# Audio_Test_Board.net
KiCad netlist of a schematic drawn in EAGLE
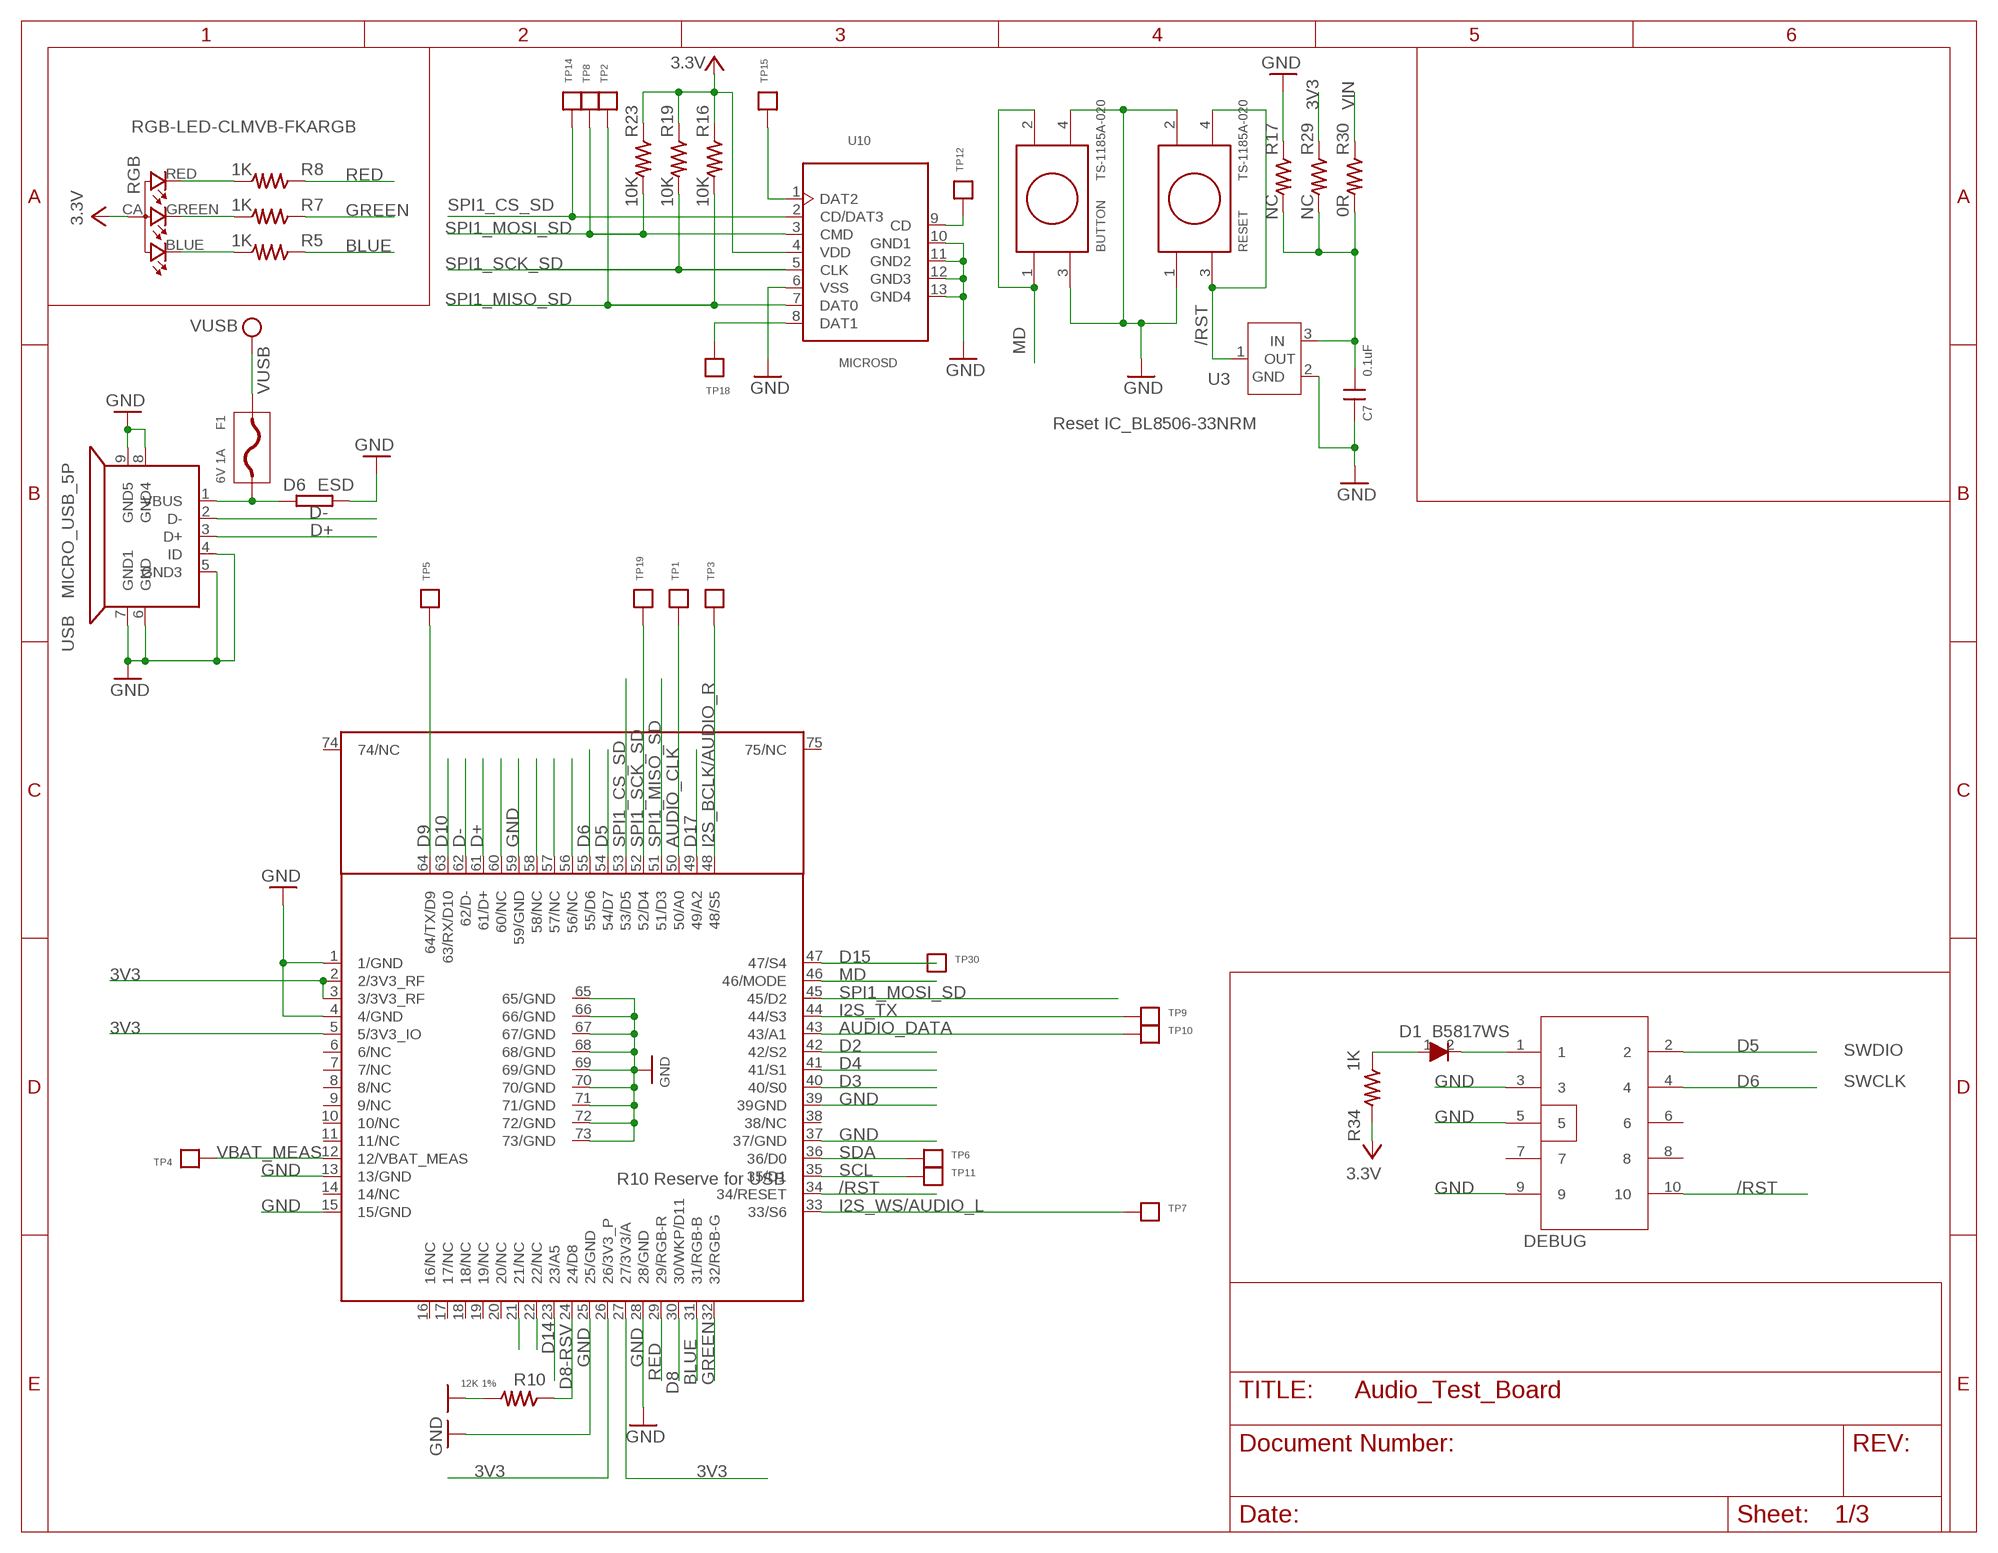
[diagram p0: schematic, sheet 1]
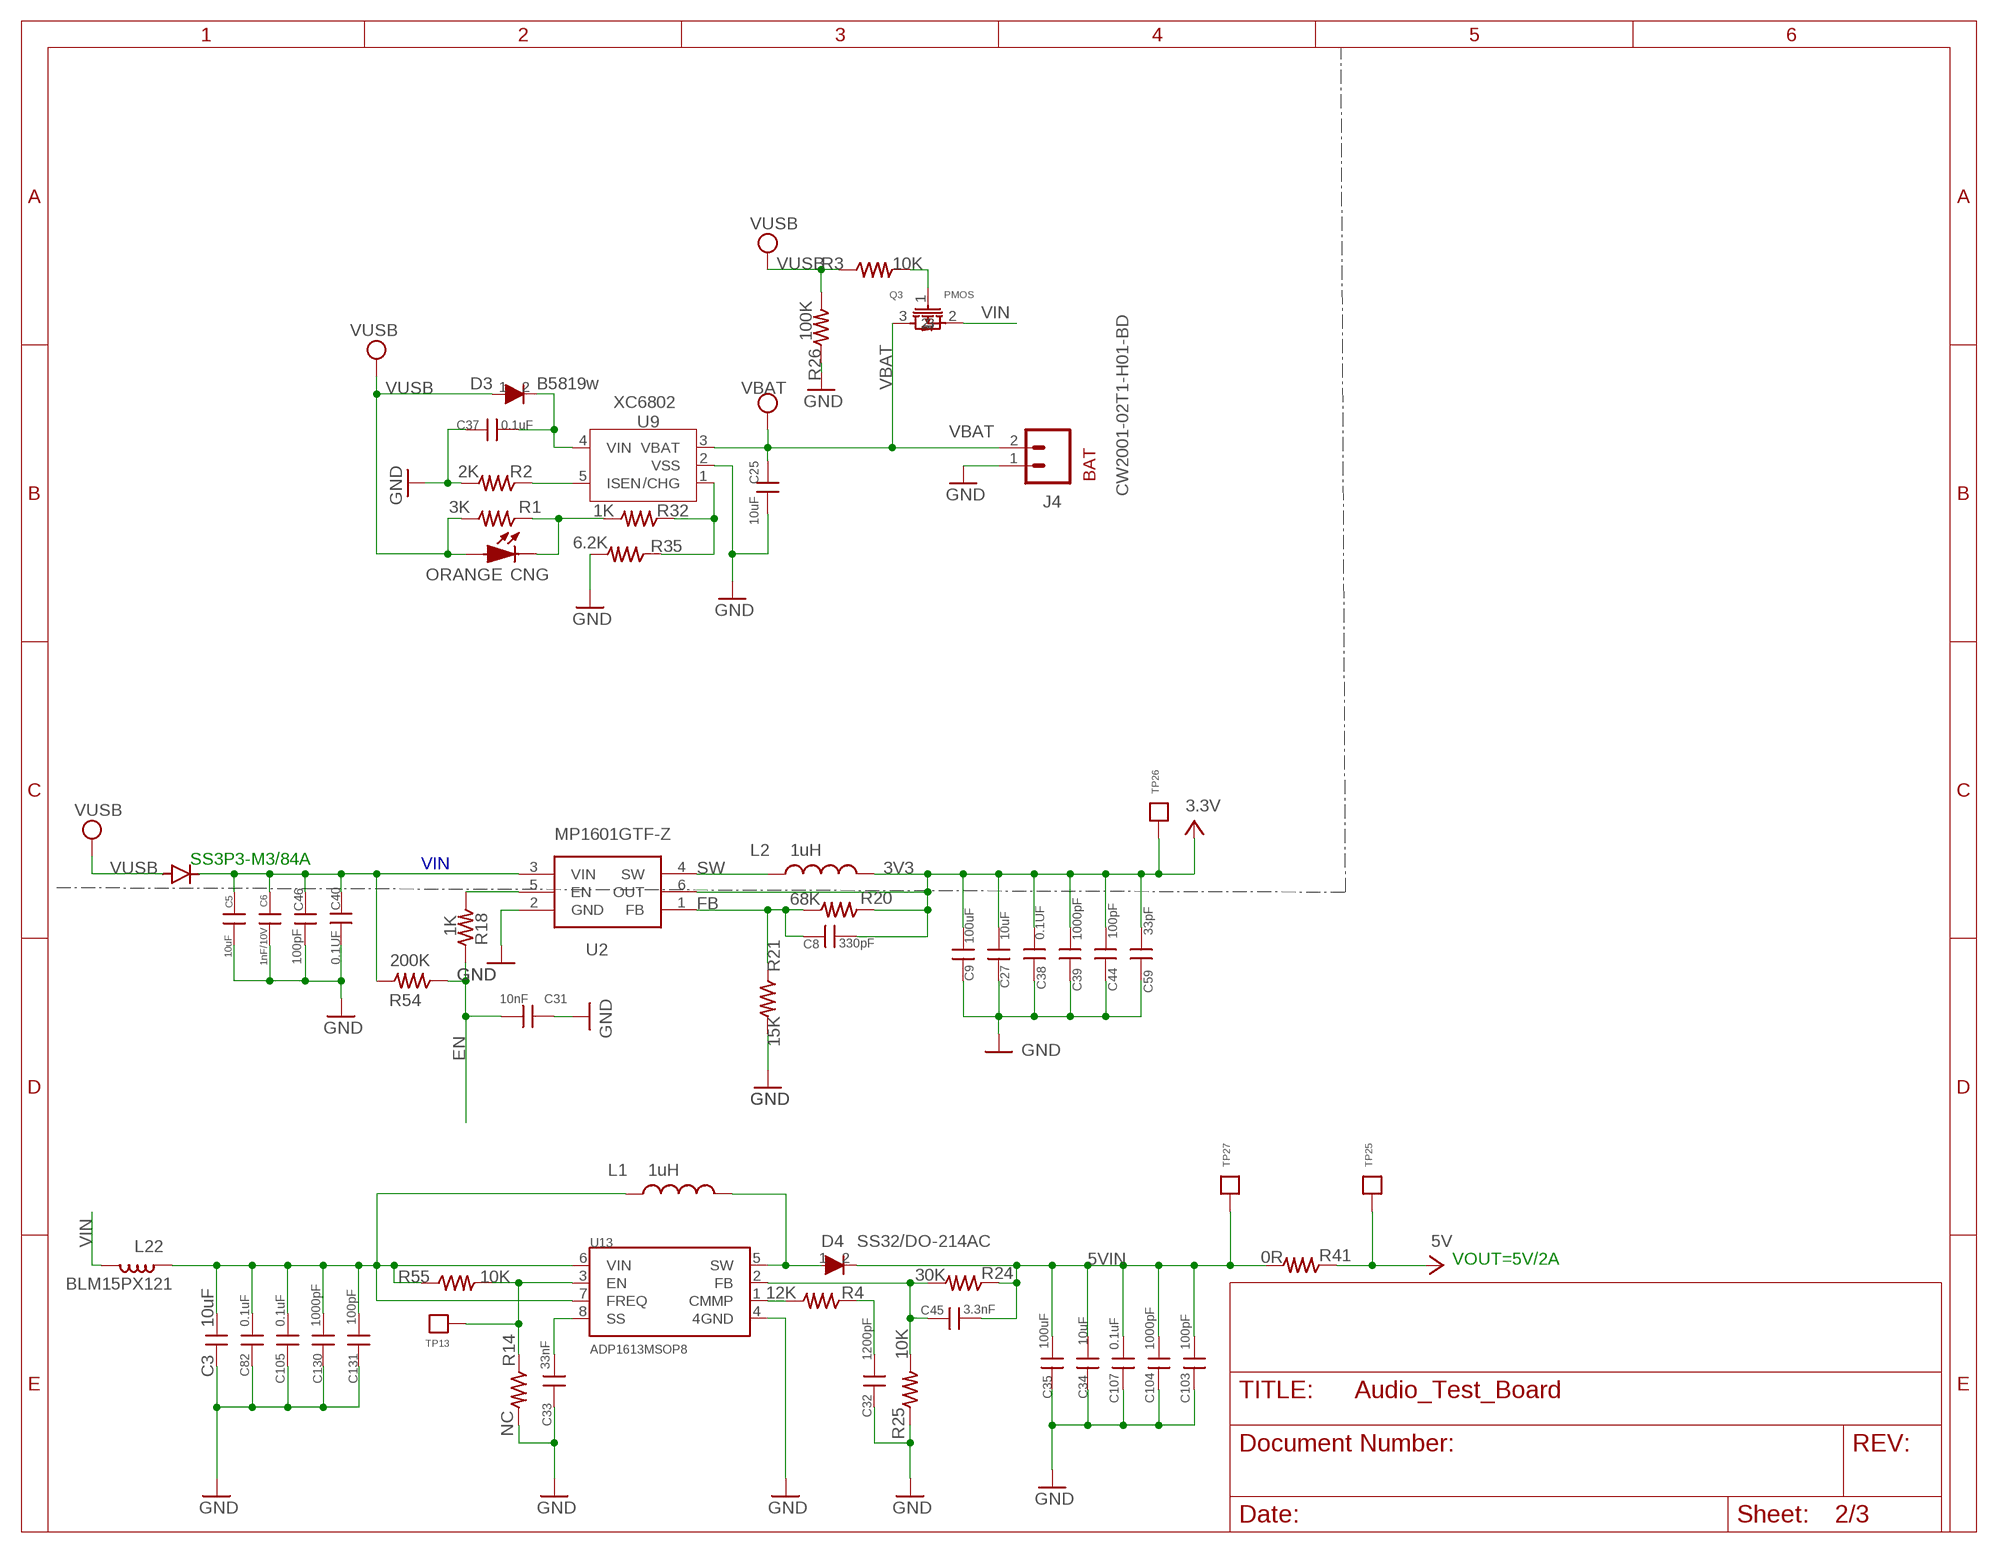
[diagram p1: schematic, sheet 2]
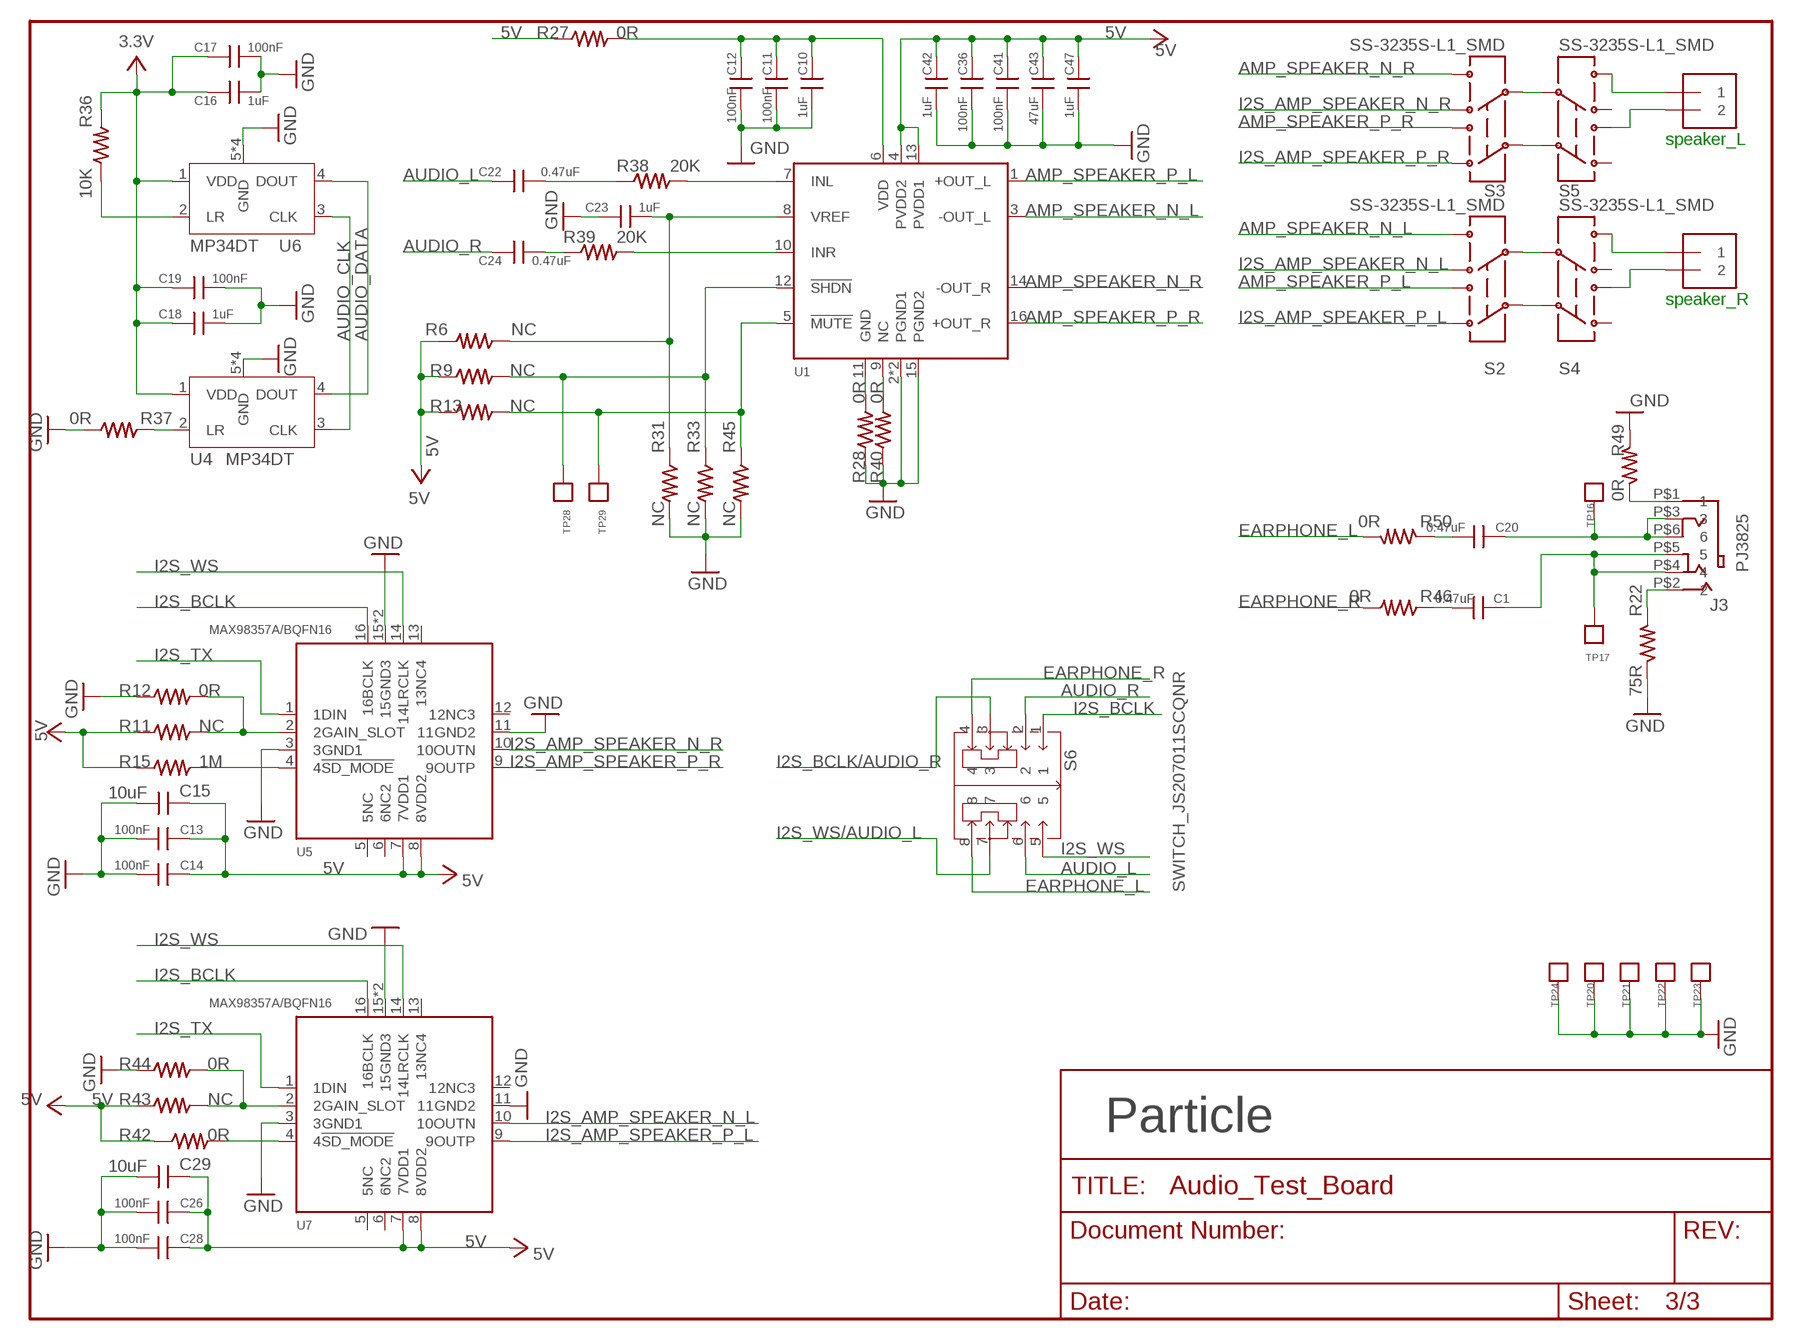
[diagram p2: schematic, sheet 3]

(export (version "E")
  (design (tool "Eeschema 10.0.6"))
  (components
    (comp (ref "C3")
      (value "10uF")
      (footprint "eagle-import:C0603")
      (libsource (lib "eagle-import") (part "particle SZ_CAPC0603"))
    )
    (comp (ref "C5")
      (value "10uF")
      (footprint "eagle-import:C0603")
      (libsource (lib "eagle-import") (part "particle SZ_CAPC0603"))
    )
    (comp (ref "C6")
      (value "1nF/10V")
      (footprint "eagle-import:C-0402")
      (libsource (lib "eagle-import") (part "particle SZ_CAP0402"))
    )
    (comp (ref "C8")
      (value "330pF")
      (footprint "eagle-import:C0402")
      (libsource (lib "eagle-import") (part "particle SZ_CAP0402A"))
    )
    (comp (ref "C9")
      (value "100uF")
      (footprint "eagle-import:C1206")
      (libsource (lib "eagle-import") (part "particle SZ_CAPC1206"))
    )
    (comp (ref "C25")
      (value "10uF")
      (footprint "eagle-import:C0805")
      (libsource (lib "eagle-import") (part "CAPC0805"))
    )
    (comp (ref "C27")
      (value "10uF")
      (footprint "eagle-import:C0603")
      (libsource (lib "eagle-import") (part "particle SZ_CAPC0603"))
    )
    (comp (ref "C31")
      (value "10nF")
      (footprint "eagle-import:C-0402")
      (libsource (lib "eagle-import") (part "particle SZ_CAP0402"))
    )
    (comp (ref "C32")
      (value "1200pF")
      (footprint "eagle-import:C-0402")
      (libsource (lib "eagle-import") (part "particle SZ_CAP0402"))
    )
    (comp (ref "C33")
      (value "33nF")
      (footprint "eagle-import:C-0402")
      (libsource (lib "eagle-import") (part "particle SZ_CAP0402"))
    )
    (comp (ref "C34")
      (value "10uF")
      (footprint "eagle-import:C0603")
      (libsource (lib "eagle-import") (part "particle SZ_CAPC0603"))
    )
    (comp (ref "C35")
      (value "100uF")
      (footprint "eagle-import:C1206")
      (libsource (lib "eagle-import") (part "particle SZ_CAPC1206"))
    )
    (comp (ref "C37")
      (value "0.1uF")
      (footprint "eagle-import:C-0402")
      (libsource (lib "eagle-import") (part "CAP0402"))
    )
    (comp (ref "C38")
      (value "0.1UF")
      (footprint "eagle-import:C-0402")
      (libsource (lib "eagle-import") (part "CAP0402"))
    )
    (comp (ref "C39")
      (value "1000pF")
      (footprint "eagle-import:C-0402")
      (libsource (lib "eagle-import") (part "CAP0402"))
    )
    (comp (ref "C40")
      (value "0.1UF")
      (footprint "eagle-import:C-0402")
      (libsource (lib "eagle-import") (part "CAP0402"))
    )
    (comp (ref "C44")
      (value "100pF")
      (footprint "eagle-import:C-0402")
      (libsource (lib "eagle-import") (part "CAP0402"))
    )
    (comp (ref "C45")
      (value "3.3nF")
      (footprint "eagle-import:C0402")
      (libsource (lib "eagle-import") (part "particle SZ_CAP0402A"))
    )
    (comp (ref "C46")
      (value "100pF")
      (footprint "eagle-import:C-0402")
      (libsource (lib "eagle-import") (part "CAP0402"))
    )
    (comp (ref "C59")
      (value "33pF")
      (footprint "eagle-import:C-0402")
      (libsource (lib "eagle-import") (part "CAP0402"))
    )
    (comp (ref "C82")
      (value "0.1uF")
      (footprint "eagle-import:C0402")
      (libsource (lib "eagle-import") (part "particle SZ_CAP0402A"))
    )
    (comp (ref "C103")
      (value "100pF")
      (footprint "eagle-import:C-0402")
      (libsource (lib "eagle-import") (part "particle SZ_CAP0402"))
    )
    (comp (ref "C104")
      (value "1000pF")
      (footprint "eagle-import:C-0402")
      (libsource (lib "eagle-import") (part "particle SZ_CAP0402"))
    )
    (comp (ref "C105")
      (value "0.1uF")
      (footprint "eagle-import:C0402")
      (libsource (lib "eagle-import") (part "particle SZ_CAP0402A"))
    )
    (comp (ref "C107")
      (value "0.1uF")
      (footprint "eagle-import:C-0402")
      (libsource (lib "eagle-import") (part "particle SZ_CAP0402"))
    )
    (comp (ref "C130")
      (value "1000pF")
      (footprint "eagle-import:C0402")
      (libsource (lib "eagle-import") (part "particle SZ_CAP0402A"))
    )
    (comp (ref "C131")
      (value "100pF")
      (footprint "eagle-import:C-0402")
      (libsource (lib "eagle-import") (part "particle SZ_CAP0402"))
    )
    (comp (ref "CNG")
      (value "ORANGE")
      (footprint "eagle-import:LED0603")
      (libsource (lib "eagle-import") (part "LED"))
    )
    (comp (ref "D2")
      (value "SS3P3-M3/84A")
      (footprint "eagle-import:DIODE-DO-220AA_NT(SMP)")
      (libsource (lib "eagle-import") (part "DIODE_NT"))
    )
    (comp (ref "D3")
      (value "B5819w")
      (footprint "eagle-import:SOD-123")
      (libsource (lib "eagle-import") (part "DIODESOD123"))
    )
    (comp (ref "D4")
      (value "SS32/DO-214AC")
      (footprint "eagle-import:DO-214AC")
      (libsource (lib "eagle-import") (part "SS32DO-214AC"))
    )
    (comp (ref "J4")
      (value "CW2001-02T1-H01-BD")
      (footprint "eagle-import:JST-2-SMD")
      (libsource (lib "eagle-import") (part "CONN_02-JST-2MM-SMT"))
    )
    (comp (ref "L1")
      (value "1uH")
      (footprint "eagle-import:INDUCTOR-VLS-E")
      (libsource (lib "eagle-import") (part "INDUCTOR-SPARKFUNVLS3012ET-4R7M"))
    )
    (comp (ref "L2")
      (value "1uH")
      (footprint "eagle-import:INDUCTOR-VLS-E")
      (libsource (lib "eagle-import") (part "INDUCTOR-SPARKFUNVLS3012ET-4R7M"))
    )
    (comp (ref "L22")
      (value "BLM15PX121")
      (footprint "eagle-import:R-0402S")
      (libsource (lib "eagle-import") (part "L-2PIN"))
    )
    (comp (ref "Q3")
      (value "PMOS")
      (footprint "eagle-import:SOT-23")
      (libsource (lib "eagle-import") (part "PMOS"))
    )
    (comp (ref "R1")
      (value "3K")
      (footprint "eagle-import:R-0402S")
      (libsource (lib "eagle-import") (part "particle SZ_RES0402S"))
    )
    (comp (ref "R2")
      (value "2K")
      (footprint "eagle-import:R-0402S")
      (libsource (lib "eagle-import") (part "particle SZ_RES0402S"))
    )
    (comp (ref "R3")
      (value "10K")
      (footprint "eagle-import:R-0402S")
      (libsource (lib "eagle-import") (part "particle SZ_RES0402S"))
    )
    (comp (ref "R4")
      (value "12K")
      (footprint "eagle-import:R-0402S")
      (libsource (lib "eagle-import") (part "particle SZ_RES0402S"))
    )
    (comp (ref "R14")
      (value "NC")
      (footprint "eagle-import:R-0402S")
      (libsource (lib "eagle-import") (part "particle SZ_RES0402S"))
    )
    (comp (ref "R18")
      (value "1K")
      (footprint "eagle-import:R-0402S")
      (libsource (lib "eagle-import") (part "particle SZ_RES0402S"))
    )
    (comp (ref "R20")
      (value "68K")
      (footprint "eagle-import:R-0402S")
      (libsource (lib "eagle-import") (part "particle SZ_RES0402S"))
    )
    (comp (ref "R21")
      (value "15K")
      (footprint "eagle-import:R-0402S")
      (libsource (lib "eagle-import") (part "particle SZ_RES0402S"))
    )
    (comp (ref "R24")
      (value "30K")
      (footprint "eagle-import:R-0402S")
      (libsource (lib "eagle-import") (part "particle SZ_RES0402S"))
    )
    (comp (ref "R25")
      (value "10K")
      (footprint "eagle-import:R-0402S")
      (libsource (lib "eagle-import") (part "particle SZ_RES0402S"))
    )
    (comp (ref "R26")
      (value "100K")
      (footprint "eagle-import:R-0402S")
      (libsource (lib "eagle-import") (part "particle SZ_RES0402S"))
    )
    (comp (ref "R32")
      (value "1K")
      (footprint "eagle-import:R-0402S")
      (libsource (lib "eagle-import") (part "particle SZ_RES0402S"))
    )
    (comp (ref "R35")
      (value "6.2K")
      (footprint "eagle-import:R-0402S")
      (libsource (lib "eagle-import") (part "particle SZ_RES0402S"))
    )
    (comp (ref "R41")
      (value "0R")
      (footprint "eagle-import:R1206")
      (libsource (lib "eagle-import") (part "particle SZ_RESR1206"))
    )
    (comp (ref "R54")
      (value "200K")
      (footprint "eagle-import:R-0402S")
      (libsource (lib "eagle-import") (part "particle SZ_RES0402S"))
    )
    (comp (ref "R55")
      (value "10K")
      (footprint "eagle-import:R-0402S")
      (libsource (lib "eagle-import") (part "particle SZ_RES0402S"))
    )
    (comp (ref "TP13")
      (value "TP")
      (footprint "eagle-import:TP0.7MM")
      (libsource (lib "eagle-import") (part "TP"))
    )
    (comp (ref "TP25")
      (value "TP")
      (footprint "eagle-import:TP0.7MM")
      (libsource (lib "eagle-import") (part "TP"))
    )
    (comp (ref "TP26")
      (value "TP")
      (footprint "eagle-import:TP0.7MM")
      (libsource (lib "eagle-import") (part "TP"))
    )
    (comp (ref "TP27")
      (value "TP")
      (footprint "eagle-import:TP0.7MM")
      (libsource (lib "eagle-import") (part "TP"))
    )
    (comp (ref "U2")
      (value "MP1601GTF-Z")
      (footprint "eagle-import:SOTFL50P160X60-6N")
      (libsource (lib "eagle-import") (part "MP1601GTF-Z"))
    )
    (comp (ref "U9")
      (value "XC6802")
      (footprint "eagle-import:SOT-23-5")
      (libsource (lib "eagle-import") (part "XC6802"))
    )
    (comp (ref "U13")
      (value "ADP1613MSOP8")
      (footprint "eagle-import:MSOP8")
      (libsource (lib "eagle-import") (part "ADP1613MSOP8"))
    )
    (comp (ref "BUTTON")
      (value "TS-1185A-020")
      (footprint "eagle-import:TS-1185A-020")
      (libsource (lib "eagle-import") (part "TS-1185A-020"))
    )
    (comp (ref "C7")
      (value "0.1uF")
      (footprint "eagle-import:C-0402")
      (libsource (lib "eagle-import") (part "CAP0402"))
    )
    (comp (ref "D1")
      (value "B5817WS")
      (footprint "eagle-import:SOD-323")
      (libsource (lib "eagle-import") (part "DIODESOD323"))
    )
    (comp (ref "D6")
      (value "ESD")
      (footprint "eagle-import:R-0402S")
      (libsource (lib "eagle-import") (part "RES0402S"))
    )
    (comp (ref "DEBUG")
      (value "CON5X2")
      (footprint "eagle-import:CON5X2_1.27")
      (libsource (lib "eagle-import") (part "CON5X2"))
    )
    (comp (ref "F1")
      (value "6V 1A")
      (footprint "eagle-import:F0805")
      (libsource (lib "eagle-import") (part "FUSE"))
    )
    (comp (ref "P2")
      (value "TRON")
      (footprint "eagle-import:TRON")
      (libsource (lib "eagle-import") (part "TRON"))
    )
    (comp (ref "R5")
      (value "1K")
      (footprint "eagle-import:R-0402S")
      (libsource (lib "eagle-import") (part "e402_v001_RES0402S"))
    )
    (comp (ref "R7")
      (value "1K")
      (footprint "eagle-import:R-0402S")
      (libsource (lib "eagle-import") (part "e402_v001_RES0402S"))
    )
    (comp (ref "R8")
      (value "1K")
      (footprint "eagle-import:R-0402S")
      (libsource (lib "eagle-import") (part "e402_v001_RES0402S"))
    )
    (comp (ref "R10")
      (value "12K 1%")
      (footprint "eagle-import:R-0402S")
      (libsource (lib "eagle-import") (part "e402_v001_RES0402S"))
    )
    (comp (ref "R16")
      (value "10K")
      (footprint "eagle-import:R-0402S")
      (libsource (lib "eagle-import") (part "e402_v001_RES0402S"))
    )
    (comp (ref "R17")
      (value "NC")
      (footprint "eagle-import:R-0402S")
      (libsource (lib "eagle-import") (part "e402_v001_RES0402S"))
    )
    (comp (ref "R19")
      (value "10K")
      (footprint "eagle-import:R-0402S")
      (libsource (lib "eagle-import") (part "e402_v001_RES0402S"))
    )
    (comp (ref "R23")
      (value "10K")
      (footprint "eagle-import:R-0402S")
      (libsource (lib "eagle-import") (part "e402_v001_RES0402S"))
    )
    (comp (ref "R29")
      (value "NC")
      (footprint "eagle-import:R-0402S")
      (libsource (lib "eagle-import") (part "e402_v001_RES0402S"))
    )
    (comp (ref "R30")
      (value "0R")
      (footprint "eagle-import:R-0402S")
      (libsource (lib "eagle-import") (part "e402_v001_RES0402S"))
    )
    (comp (ref "R34")
      (value "1K")
      (footprint "eagle-import:R-0402S")
      (libsource (lib "eagle-import") (part "particle SZ_RES0402S"))
    )
    (comp (ref "RESET")
      (value "TS-1185A-020")
      (footprint "eagle-import:TS-1185A-020")
      (libsource (lib "eagle-import") (part "TS-1185A-020"))
    )
    (comp (ref "RGB")
      (value "RGB-LED-CLMVB-FKARGB")
      (footprint "eagle-import:PLCC4-2MM-RGB")
      (libsource (lib "eagle-import") (part "RGB-LED-CLMVB-FKARGB"))
    )
    (comp (ref "TP1")
      (value "TP")
      (footprint "eagle-import:TP0.7MM")
      (libsource (lib "eagle-import") (part "TP"))
    )
    (comp (ref "TP2")
      (value "TP")
      (footprint "eagle-import:TP0.7MM")
      (libsource (lib "eagle-import") (part "TP"))
    )
    (comp (ref "TP3")
      (value "TP")
      (footprint "eagle-import:TP0.7MM")
      (libsource (lib "eagle-import") (part "TP"))
    )
    (comp (ref "TP4")
      (value "TP")
      (footprint "eagle-import:TP0.7MM")
      (libsource (lib "eagle-import") (part "TP"))
    )
    (comp (ref "TP5")
      (value "TP")
      (footprint "eagle-import:TP0.7MM")
      (libsource (lib "eagle-import") (part "TP"))
    )
    (comp (ref "TP6")
      (value "TP")
      (footprint "eagle-import:TP0.7MM")
      (libsource (lib "eagle-import") (part "TP"))
    )
    (comp (ref "TP7")
      (value "TP")
      (footprint "eagle-import:TP0.7MM")
      (libsource (lib "eagle-import") (part "TP"))
    )
    (comp (ref "TP8")
      (value "TP")
      (footprint "eagle-import:TP0.7MM")
      (libsource (lib "eagle-import") (part "TP"))
    )
    (comp (ref "TP9")
      (value "TP")
      (footprint "eagle-import:TP0.7MM")
      (libsource (lib "eagle-import") (part "TP"))
    )
    (comp (ref "TP10")
      (value "TP")
      (footprint "eagle-import:TP0.7MM")
      (libsource (lib "eagle-import") (part "TP"))
    )
    (comp (ref "TP11")
      (value "TP")
      (footprint "eagle-import:TP0.7MM")
      (libsource (lib "eagle-import") (part "TP"))
    )
    (comp (ref "TP12")
      (value "TP")
      (footprint "eagle-import:TP0.7MM")
      (libsource (lib "eagle-import") (part "TP"))
    )
    (comp (ref "TP14")
      (value "TP")
      (footprint "eagle-import:TP0.7MM")
      (libsource (lib "eagle-import") (part "TP"))
    )
    (comp (ref "TP15")
      (value "TP")
      (footprint "eagle-import:TP0.7MM")
      (libsource (lib "eagle-import") (part "TP"))
    )
    (comp (ref "TP18")
      (value "TP")
      (footprint "eagle-import:TP0.7MM")
      (libsource (lib "eagle-import") (part "TP"))
    )
    (comp (ref "TP19")
      (value "TP")
      (footprint "eagle-import:TP0.7MM")
      (libsource (lib "eagle-import") (part "TP"))
    )
    (comp (ref "TP30")
      (value "TP")
      (footprint "eagle-import:TP0.7MM")
      (libsource (lib "eagle-import") (part "TP"))
    )
    (comp (ref "U3")
      (value "Reset IC_BL8506-33NRM")
      (footprint "eagle-import:PARTICLE-SZ_SOT-23")
      (libsource (lib "eagle-import") (part "PARTICLE-SZ_BL8506"))
    )
    (comp (ref "U10")
      (value "MICROSD")
      (footprint "eagle-import:MICROSD")
      (libsource (lib "eagle-import") (part "MICROSD"))
    )
    (comp (ref "USB")
      (value "MICRO_USB_5P")
      (footprint "eagle-import:MICRO_USB")
      (libsource (lib "eagle-import") (part "MICRO_USBMICRO_USB"))
    )
    (comp (ref "C1")
      (value "0.47uF")
      (footprint "eagle-import:C0805")
      (libsource (lib "eagle-import") (part "particle SZ_CAPC0805"))
    )
    (comp (ref "C10")
      (value "1uF")
      (footprint "eagle-import:C-0402")
      (libsource (lib "eagle-import") (part "particle SZ_CAP0402"))
    )
    (comp (ref "C11")
      (value "100nF")
      (footprint "eagle-import:C-0402")
      (libsource (lib "eagle-import") (part "particle SZ_CAP0402"))
    )
    (comp (ref "C12")
      (value "100nF")
      (footprint "eagle-import:C-0402")
      (libsource (lib "eagle-import") (part "particle SZ_CAP0402"))
    )
    (comp (ref "C13")
      (value "100nF")
      (footprint "eagle-import:C-0402")
      (libsource (lib "eagle-import") (part "particle SZ_CAP0402"))
    )
    (comp (ref "C14")
      (value "100nF")
      (footprint "eagle-import:C-0402")
      (libsource (lib "eagle-import") (part "particle SZ_CAP0402"))
    )
    (comp (ref "C15")
      (value "10uF")
      (footprint "eagle-import:C0603")
      (libsource (lib "eagle-import") (part "particle SZ_CAPC0603"))
    )
    (comp (ref "C16")
      (value "1uF")
      (footprint "eagle-import:C-0402")
      (libsource (lib "eagle-import") (part "particle SZ_CAP0402"))
    )
    (comp (ref "C17")
      (value "100nF")
      (footprint "eagle-import:C-0402")
      (libsource (lib "eagle-import") (part "particle SZ_CAP0402"))
    )
    (comp (ref "C18")
      (value "1uF")
      (footprint "eagle-import:C-0402")
      (libsource (lib "eagle-import") (part "particle SZ_CAP0402"))
    )
    (comp (ref "C19")
      (value "100nF")
      (footprint "eagle-import:C-0402")
      (libsource (lib "eagle-import") (part "particle SZ_CAP0402"))
    )
    (comp (ref "C20")
      (value "0.47uF")
      (footprint "eagle-import:C0805")
      (libsource (lib "eagle-import") (part "particle SZ_CAPC0805"))
    )
    (comp (ref "C22")
      (value "0.47uF")
      (footprint "eagle-import:C-0402")
      (libsource (lib "eagle-import") (part "particle SZ_CAP0402"))
    )
    (comp (ref "C23")
      (value "1uF")
      (footprint "eagle-import:C-0402")
      (libsource (lib "eagle-import") (part "particle SZ_CAP0402"))
    )
    (comp (ref "C24")
      (value "0.47uF")
      (footprint "eagle-import:C-0402")
      (libsource (lib "eagle-import") (part "particle SZ_CAP0402"))
    )
    (comp (ref "C26")
      (value "100nF")
      (footprint "eagle-import:C-0402")
      (libsource (lib "eagle-import") (part "particle SZ_CAP0402"))
    )
    (comp (ref "C28")
      (value "100nF")
      (footprint "eagle-import:C-0402")
      (libsource (lib "eagle-import") (part "particle SZ_CAP0402"))
    )
    (comp (ref "C29")
      (value "10uF")
      (footprint "eagle-import:C0603")
      (libsource (lib "eagle-import") (part "particle SZ_CAPC0603"))
    )
    (comp (ref "C36")
      (value "100nF")
      (footprint "eagle-import:C-0402")
      (libsource (lib "eagle-import") (part "particle SZ_CAP0402"))
    )
    (comp (ref "C41")
      (value "100nF")
      (footprint "eagle-import:C-0402")
      (libsource (lib "eagle-import") (part "particle SZ_CAP0402"))
    )
    (comp (ref "C42")
      (value "1uF")
      (footprint "eagle-import:C-0402")
      (libsource (lib "eagle-import") (part "particle SZ_CAP0402"))
    )
    (comp (ref "C43")
      (value "47uF")
      (footprint "eagle-import:C1206")
      (libsource (lib "eagle-import") (part "particle SZ_CAPC1206"))
    )
    (comp (ref "C47")
      (value "1uF")
      (footprint "eagle-import:C-0402")
      (libsource (lib "eagle-import") (part "particle SZ_CAP0402"))
    )
    (comp (ref "J1")
      (value "1X2-3.5MM")
      (footprint "eagle-import:1X2-3.5MM")
      (libsource (lib "eagle-import") (part "1X2-3.5MM"))
    )
    (comp (ref "J2")
      (value "1X2-3.5MM")
      (footprint "eagle-import:1X2-3.5MM")
      (libsource (lib "eagle-import") (part "1X2-3.5MM"))
    )
    (comp (ref "J3")
      (value "PJ3825")
      (footprint "eagle-import:PJ3825")
      (libsource (lib "eagle-import") (part "PJ3825"))
    )
    (comp (ref "R6")
      (value "NC")
      (footprint "eagle-import:R-0402S")
      (libsource (lib "eagle-import") (part "particle SZ_RES0402S"))
    )
    (comp (ref "R9")
      (value "NC")
      (footprint "eagle-import:R-0402S")
      (libsource (lib "eagle-import") (part "particle SZ_RES0402S"))
    )
    (comp (ref "R11")
      (value "NC")
      (footprint "eagle-import:R-0402S")
      (libsource (lib "eagle-import") (part "particle SZ_RES0402S"))
    )
    (comp (ref "R12")
      (value "0R")
      (footprint "eagle-import:R-0402S")
      (libsource (lib "eagle-import") (part "particle SZ_RES0402S"))
    )
    (comp (ref "R13")
      (value "NC")
      (footprint "eagle-import:R-0402S")
      (libsource (lib "eagle-import") (part "particle SZ_RES0402S"))
    )
    (comp (ref "R15")
      (value "1M")
      (footprint "eagle-import:R-0402S")
      (libsource (lib "eagle-import") (part "particle SZ_RES0402S"))
    )
    (comp (ref "R22")
      (value "75R")
      (footprint "eagle-import:R-0402S")
      (libsource (lib "eagle-import") (part "particle SZ_RES0402S"))
    )
    (comp (ref "R27")
      (value "0R")
      (footprint "eagle-import:R-0402S")
      (libsource (lib "eagle-import") (part "particle SZ_RES0402S"))
    )
    (comp (ref "R28")
      (value "0R")
      (footprint "eagle-import:R-0402S")
      (libsource (lib "eagle-import") (part "particle SZ_RES0402S"))
    )
    (comp (ref "R31")
      (value "NC")
      (footprint "eagle-import:R-0402S")
      (libsource (lib "eagle-import") (part "particle SZ_RES0402S"))
    )
    (comp (ref "R33")
      (value "NC")
      (footprint "eagle-import:R-0402S")
      (libsource (lib "eagle-import") (part "particle SZ_RES0402S"))
    )
    (comp (ref "R36")
      (value "10K")
      (footprint "eagle-import:R-0402S")
      (libsource (lib "eagle-import") (part "particle SZ_RES0402S"))
    )
    (comp (ref "R37")
      (value "0R")
      (footprint "eagle-import:R-0402S")
      (libsource (lib "eagle-import") (part "particle SZ_RES0402S"))
    )
    (comp (ref "R38")
      (value "20K")
      (footprint "eagle-import:R-0402S")
      (libsource (lib "eagle-import") (part "particle SZ_RES0402S"))
    )
    (comp (ref "R39")
      (value "20K")
      (footprint "eagle-import:R-0402S")
      (libsource (lib "eagle-import") (part "particle SZ_RES0402S"))
    )
    (comp (ref "R40")
      (value "0R")
      (footprint "eagle-import:R-0402S")
      (libsource (lib "eagle-import") (part "particle SZ_RES0402S"))
    )
    (comp (ref "R42")
      (value "0R")
      (footprint "eagle-import:R-0402S")
      (libsource (lib "eagle-import") (part "particle SZ_RES0402S"))
    )
    (comp (ref "R43")
      (value "NC")
      (footprint "eagle-import:R-0402S")
      (libsource (lib "eagle-import") (part "particle SZ_RES0402S"))
    )
    (comp (ref "R44")
      (value "0R")
      (footprint "eagle-import:R-0402S")
      (libsource (lib "eagle-import") (part "particle SZ_RES0402S"))
    )
    (comp (ref "R45")
      (value "NC")
      (footprint "eagle-import:R-0402S")
      (libsource (lib "eagle-import") (part "particle SZ_RES0402S"))
    )
    (comp (ref "R46")
      (value "0R")
      (footprint "eagle-import:R0805")
      (libsource (lib "eagle-import") (part "particle SZ_RESR0805"))
    )
    (comp (ref "R49")
      (value "0R")
      (footprint "eagle-import:R0805")
      (libsource (lib "eagle-import") (part "particle SZ_RESR0805"))
    )
    (comp (ref "R50")
      (value "0R")
      (footprint "eagle-import:R0805")
      (libsource (lib "eagle-import") (part "particle SZ_RESR0805"))
    )
    (comp (ref "S2")
      (value "SS-3235S-L1_SMD")
      (footprint "eagle-import:SS-3235S-L1_SMD")
      (libsource (lib "eagle-import") (part "SS-3235S-L1_SMD"))
    )
    (comp (ref "S3")
      (value "SS-3235S-L1_SMD")
      (footprint "eagle-import:SS-3235S-L1_SMD")
      (libsource (lib "eagle-import") (part "SS-3235S-L1_SMD"))
    )
    (comp (ref "S4")
      (value "SS-3235S-L1_SMD")
      (footprint "eagle-import:SS-3235S-L1_SMD")
      (libsource (lib "eagle-import") (part "SS-3235S-L1_SMD"))
    )
    (comp (ref "S5")
      (value "SS-3235S-L1_SMD")
      (footprint "eagle-import:SS-3235S-L1_SMD")
      (libsource (lib "eagle-import") (part "SS-3235S-L1_SMD"))
    )
    (comp (ref "S6")
      (value "SWITCH_JS207011SCQNR")
      (footprint "eagle-import:SWITCH-JS207011SCQNR")
      (libsource (lib "eagle-import") (part "SWITCH_JS207011SCQNR"))
    )
    (comp (ref "TP16")
      (value "TP")
      (footprint "eagle-import:TP0.7MM")
      (libsource (lib "eagle-import") (part "TP"))
    )
    (comp (ref "TP17")
      (value "TP")
      (footprint "eagle-import:TP0.7MM")
      (libsource (lib "eagle-import") (part "TP"))
    )
    (comp (ref "TP20")
      (value "TP")
      (footprint "eagle-import:TP0.7MM")
      (libsource (lib "eagle-import") (part "TP"))
    )
    (comp (ref "TP21")
      (value "TP")
      (footprint "eagle-import:TP0.7MM")
      (libsource (lib "eagle-import") (part "TP"))
    )
    (comp (ref "TP22")
      (value "TP")
      (footprint "eagle-import:TP0.7MM")
      (libsource (lib "eagle-import") (part "TP"))
    )
    (comp (ref "TP23")
      (value "TP")
      (footprint "eagle-import:TP0.7MM")
      (libsource (lib "eagle-import") (part "TP"))
    )
    (comp (ref "TP24")
      (value "TP")
      (footprint "eagle-import:TP0.7MM")
      (libsource (lib "eagle-import") (part "TP"))
    )
    (comp (ref "TP28")
      (value "TP")
      (footprint "eagle-import:TP0.7MM")
      (libsource (lib "eagle-import") (part "TP"))
    )
    (comp (ref "TP29")
      (value "TP")
      (footprint "eagle-import:TP0.7MM")
      (libsource (lib "eagle-import") (part "TP"))
    )
    (comp (ref "U1")
      (value "PARTICLE-SZ_PAM8403DRSOP16")
      (footprint "eagle-import:PARTICLE-SZ_SOIC16")
      (libsource (lib "eagle-import") (part "PARTICLE-SZ_PAM8403DRSOP16"))
    )
    (comp (ref "U4")
      (value "MP34DT")
      (footprint "eagle-import:MP34DT")
      (libsource (lib "eagle-import") (part "MP34DT"))
    )
    (comp (ref "U5")
      (value "MAX98357A/BQFN16")
      (footprint "eagle-import:QFN16")
      (libsource (lib "eagle-import") (part "MAX98357A/BQFN16"))
    )
    (comp (ref "U6")
      (value "MP34DT")
      (footprint "eagle-import:MP34DT")
      (libsource (lib "eagle-import") (part "MP34DT"))
    )
    (comp (ref "U7")
      (value "MAX98357A/BQFN16")
      (footprint "eagle-import:QFN16")
      (libsource (lib "eagle-import") (part "MAX98357A/BQFN16"))
    )
  )
  (nets
    (net (code "1") (name "3V3") (class "Default")
      (node (ref "C16") (pin "2") (pinfunction "2_2") (pintype "bidirectional"))
      (node (ref "C17") (pin "2") (pinfunction "2_2") (pintype "bidirectional"))
      (node (ref "C18") (pin "2") (pinfunction "2_2") (pintype "bidirectional"))
      (node (ref "C19") (pin "2") (pinfunction "2_2") (pintype "bidirectional"))
      (node (ref "C27") (pin "1") (pinfunction "1_1") (pintype "bidirectional"))
      (node (ref "C38") (pin "2") (pinfunction "2_2") (pintype "bidirectional"))
      (node (ref "C39") (pin "2") (pinfunction "2_2") (pintype "bidirectional"))
      (node (ref "C44") (pin "2") (pinfunction "2_2") (pintype "bidirectional"))
      (node (ref "C59") (pin "2") (pinfunction "2_2") (pintype "bidirectional"))
      (node (ref "C8") (pin "2") (pinfunction "2_2") (pintype "bidirectional"))
      (node (ref "C9") (pin "1") (pinfunction "1_1") (pintype "bidirectional"))
      (node (ref "L2") (pin "P$2") (pinfunction "2_P$2") (pintype "passive"))
      (node (ref "P2") (pin "2") (pinfunction "2/3V3_RF_2") (pintype "bidirectional"))
      (node (ref "P2") (pin "26") (pinfunction "26/3V3_P_26") (pintype "bidirectional"))
      (node (ref "P2") (pin "27") (pinfunction "27/3V3/A_27") (pintype "bidirectional"))
      (node (ref "P2") (pin "3") (pinfunction "3/3V3_RF_3") (pintype "bidirectional"))
      (node (ref "P2") (pin "5") (pinfunction "5/3V3_IO_5") (pintype "bidirectional"))
      (node (ref "R16") (pin "1") (pinfunction "1_1") (pintype "bidirectional"))
      (node (ref "R19") (pin "1") (pinfunction "1_1") (pintype "bidirectional"))
      (node (ref "R20") (pin "1") (pinfunction "1_1") (pintype "bidirectional"))
      (node (ref "R23") (pin "1") (pinfunction "1_1") (pintype "bidirectional"))
      (node (ref "R29") (pin "1") (pinfunction "1_1") (pintype "bidirectional"))
      (node (ref "R34") (pin "2") (pinfunction "2_2") (pintype "bidirectional"))
      (node (ref "R36") (pin "2") (pinfunction "2_2") (pintype "bidirectional"))
      (node (ref "RGB") (pin "CA") (pinfunction "1_CA") (pintype "passive"))
      (node (ref "TP26") (pin "P$1") (pinfunction "1_P$1") (pintype "bidirectional"))
      (node (ref "U10") (pin "4") (pinfunction "VDD_4") (pintype "power_in"))
      (node (ref "U2") (pin "6") (pinfunction "OUT_6") (pintype "bidirectional"))
      (node (ref "U4") (pin "1") (pinfunction "VDD_1") (pintype "bidirectional"))
      (node (ref "U6") (pin "1") (pinfunction "VDD_1") (pintype "bidirectional"))
    )
    (net (code "2") (name "5V") (class "Default")
      (node (ref "C13") (pin "2") (pinfunction "2_2") (pintype "bidirectional"))
      (node (ref "C14") (pin "2") (pinfunction "2_2") (pintype "bidirectional"))
      (node (ref "C15") (pin "1") (pinfunction "1_1") (pintype "bidirectional"))
      (node (ref "C26") (pin "2") (pinfunction "2_2") (pintype "bidirectional"))
      (node (ref "C28") (pin "2") (pinfunction "2_2") (pintype "bidirectional"))
      (node (ref "C29") (pin "1") (pinfunction "1_1") (pintype "bidirectional"))
      (node (ref "C36") (pin "2") (pinfunction "2_2") (pintype "bidirectional"))
      (node (ref "C41") (pin "2") (pinfunction "2_2") (pintype "bidirectional"))
      (node (ref "C42") (pin "2") (pinfunction "2_2") (pintype "bidirectional"))
      (node (ref "C43") (pin "2") (pinfunction "2_2") (pintype "bidirectional"))
      (node (ref "C47") (pin "2") (pinfunction "2_2") (pintype "bidirectional"))
      (node (ref "R11") (pin "1") (pinfunction "1_1") (pintype "bidirectional"))
      (node (ref "R13") (pin "1") (pinfunction "1_1") (pintype "bidirectional"))
      (node (ref "R15") (pin "1") (pinfunction "1_1") (pintype "bidirectional"))
      (node (ref "R27") (pin "1") (pinfunction "1_1") (pintype "bidirectional"))
      (node (ref "R41") (pin "1") (pinfunction "1_1") (pintype "bidirectional"))
      (node (ref "R42") (pin "1") (pinfunction "1_1") (pintype "bidirectional"))
      (node (ref "R43") (pin "1") (pinfunction "1_1") (pintype "bidirectional"))
      (node (ref "R6") (pin "2") (pinfunction "2_2") (pintype "bidirectional"))
      (node (ref "R9") (pin "1") (pinfunction "1_1") (pintype "bidirectional"))
      (node (ref "TP25") (pin "P$1") (pinfunction "1_P$1") (pintype "bidirectional"))
      (node (ref "U1") (pin "13") (pinfunction "PVDD1_13") (pintype "bidirectional"))
      (node (ref "U1") (pin "4") (pinfunction "PVDD2_4") (pintype "bidirectional"))
      (node (ref "U5") (pin "7") (pinfunction "7VDD1_7") (pintype "bidirectional"))
      (node (ref "U5") (pin "8") (pinfunction "8VDD2_8") (pintype "bidirectional"))
      (node (ref "U7") (pin "7") (pinfunction "7VDD1_7") (pintype "bidirectional"))
      (node (ref "U7") (pin "8") (pinfunction "8VDD2_8") (pintype "bidirectional"))
    )
    (net (code "3") (name "5VIN") (class "Default")
      (node (ref "C103") (pin "1") (pinfunction "1_1") (pintype "bidirectional"))
      (node (ref "C104") (pin "1") (pinfunction "1_1") (pintype "bidirectional"))
      (node (ref "C107") (pin "1") (pinfunction "1_1") (pintype "bidirectional"))
      (node (ref "C34") (pin "1") (pinfunction "1_1") (pintype "bidirectional"))
      (node (ref "C35") (pin "1") (pinfunction "1_1") (pintype "bidirectional"))
      (node (ref "C45") (pin "2") (pinfunction "2_2") (pintype "bidirectional"))
      (node (ref "D4") (pin "2") (pinfunction "P$2_2") (pintype "bidirectional"))
      (node (ref "R24") (pin "1") (pinfunction "1_1") (pintype "bidirectional"))
      (node (ref "R41") (pin "2") (pinfunction "2_2") (pintype "bidirectional"))
      (node (ref "TP27") (pin "P$1") (pinfunction "1_P$1") (pintype "bidirectional"))
    )
    (net (code "4") (name "AMP_SPEAKER_N_L") (class "Default")
      (node (ref "S2") (pin "4") (pinfunction "4_4") (pintype "bidirectional"))
      (node (ref "U1") (pin "3") (pinfunction "-OUT_L_3") (pintype "bidirectional"))
    )
    (net (code "5") (name "AMP_SPEAKER_N_R") (class "Default")
      (node (ref "S3") (pin "4") (pinfunction "4_4") (pintype "bidirectional"))
      (node (ref "U1") (pin "14") (pinfunction "-OUT_R_14") (pintype "bidirectional"))
    )
    (net (code "6") (name "AMP_SPEAKER_P_L") (class "Default")
      (node (ref "S2") (pin "1") (pinfunction "1_1") (pintype "bidirectional"))
      (node (ref "U1") (pin "1") (pinfunction "+OUT_L_1") (pintype "bidirectional"))
    )
    (net (code "7") (name "AMP_SPEAKER_P_R") (class "Default")
      (node (ref "S3") (pin "1") (pinfunction "1_1") (pintype "bidirectional"))
      (node (ref "U1") (pin "16") (pinfunction "+OUT_R_16") (pintype "bidirectional"))
    )
    (net (code "8") (name "AUDIO_CLK") (class "Default")
      (node (ref "P2") (pin "50") (pinfunction "50/A0_50") (pintype "bidirectional"))
      (node (ref "TP1") (pin "P$1") (pinfunction "1_P$1") (pintype "bidirectional"))
      (node (ref "U4") (pin "3") (pinfunction "CLK_3") (pintype "bidirectional"))
      (node (ref "U6") (pin "3") (pinfunction "CLK_3") (pintype "bidirectional"))
    )
    (net (code "9") (name "AUDIO_DATA") (class "Default")
      (node (ref "P2") (pin "43") (pinfunction "43/A1_43") (pintype "bidirectional"))
      (node (ref "TP10") (pin "P$1") (pinfunction "1_P$1") (pintype "bidirectional"))
      (node (ref "U4") (pin "4") (pinfunction "DOUT_4") (pintype "bidirectional"))
      (node (ref "U6") (pin "4") (pinfunction "DOUT_4") (pintype "bidirectional"))
    )
    (net (code "10") (name "AUDIO_L") (class "Default")
      (node (ref "C22") (pin "2") (pinfunction "2_2") (pintype "bidirectional"))
      (node (ref "S6") (pin "6") (pinfunction "6_6") (pintype "bidirectional"))
    )
    (net (code "11") (name "AUDIO_R") (class "Default")
      (node (ref "C24") (pin "2") (pinfunction "2_2") (pintype "bidirectional"))
      (node (ref "S6") (pin "2") (pinfunction "2_2") (pintype "bidirectional"))
    )
    (net (code "12") (name "BLUE") (class "Default")
      (node (ref "P2") (pin "31") (pinfunction "31/RGB-B_31") (pintype "bidirectional"))
      (node (ref "R5") (pin "1") (pinfunction "1_1") (pintype "bidirectional"))
    )
    (net (code "13") (name "D+") (class "Default")
      (node (ref "P2") (pin "61") (pinfunction "61/D+_61") (pintype "bidirectional"))
      (node (ref "USB") (pin "3") (pinfunction "D+_3") (pintype "bidirectional"))
    )
    (net (code "14") (name "D-") (class "Default")
      (node (ref "P2") (pin "62") (pinfunction "62/D-_62") (pintype "bidirectional"))
      (node (ref "USB") (pin "2") (pinfunction "D-_2") (pintype "bidirectional"))
    )
    (net (code "15") (name "D2") (class "Default")
      (node (ref "P2") (pin "42") (pinfunction "42/S2_42") (pintype "bidirectional"))
    )
    (net (code "16") (name "D3") (class "Default")
      (node (ref "P2") (pin "40") (pinfunction "40/S0_40") (pintype "bidirectional"))
    )
    (net (code "17") (name "D4") (class "Default")
      (node (ref "P2") (pin "41") (pinfunction "41/S1_41") (pintype "bidirectional"))
    )
    (net (code "18") (name "D5") (class "Default")
      (node (ref "DEBUG") (pin "2") (pinfunction "2_2") (pintype "bidirectional"))
      (node (ref "P2") (pin "54") (pinfunction "54/D7_54") (pintype "bidirectional"))
    )
    (net (code "19") (name "D6") (class "Default")
      (node (ref "DEBUG") (pin "4") (pinfunction "4_4") (pintype "bidirectional"))
      (node (ref "P2") (pin "55") (pinfunction "55/D6_55") (pintype "bidirectional"))
    )
    (net (code "20") (name "D8") (class "Default")
      (node (ref "P2") (pin "30") (pinfunction "30/WKP/D11_30") (pintype "bidirectional"))
    )
    (net (code "21") (name "D8-RSV") (class "Default")
      (node (ref "P2") (pin "24") (pinfunction "24/D8_24") (pintype "bidirectional"))
      (node (ref "R10") (pin "1") (pinfunction "1_1") (pintype "bidirectional"))
    )
    (net (code "22") (name "D9") (class "Default")
      (node (ref "P2") (pin "64") (pinfunction "64/TX/D9_64") (pintype "bidirectional"))
      (node (ref "TP5") (pin "P$1") (pinfunction "1_P$1") (pintype "bidirectional"))
    )
    (net (code "23") (name "D10") (class "Default")
      (node (ref "P2") (pin "63") (pinfunction "63/RX/D10_63") (pintype "bidirectional"))
    )
    (net (code "24") (name "D14") (class "Default")
      (node (ref "P2") (pin "23") (pinfunction "23/A5_23") (pintype "bidirectional"))
    )
    (net (code "25") (name "D15") (class "Default")
      (node (ref "P2") (pin "47") (pinfunction "47/S4_47") (pintype "bidirectional"))
      (node (ref "TP30") (pin "P$1") (pinfunction "1_P$1") (pintype "bidirectional"))
    )
    (net (code "26") (name "D17") (class "Default")
      (node (ref "P2") (pin "49") (pinfunction "49/A2_49") (pintype "bidirectional"))
    )
    (net (code "27") (name "EARPHONE_L") (class "Default")
      (node (ref "R50") (pin "2") (pinfunction "2_2") (pintype "bidirectional"))
      (node (ref "S6") (pin "8") (pinfunction "8_8") (pintype "bidirectional"))
    )
    (net (code "28") (name "EARPHONE_R") (class "Default")
      (node (ref "R46") (pin "2") (pinfunction "2_2") (pintype "bidirectional"))
      (node (ref "S6") (pin "4") (pinfunction "4_4") (pintype "bidirectional"))
    )
    (net (code "29") (name "EN") (class "Default")
      (node (ref "C31") (pin "2") (pinfunction "2_2") (pintype "bidirectional"))
      (node (ref "R18") (pin "1") (pinfunction "1_1") (pintype "bidirectional"))
      (node (ref "R54") (pin "1") (pinfunction "1_1") (pintype "bidirectional"))
    )
    (net (code "30") (name "FB") (class "Default")
      (node (ref "C8") (pin "1") (pinfunction "1_1") (pintype "bidirectional"))
      (node (ref "R20") (pin "2") (pinfunction "2_2") (pintype "bidirectional"))
      (node (ref "R21") (pin "1") (pinfunction "1_1") (pintype "bidirectional"))
      (node (ref "U2") (pin "1") (pinfunction "FB_1") (pintype "bidirectional"))
    )
    (net (code "31") (name "GND") (class "Default")
      (node (ref "BUTTON") (pin "3") (pinfunction "P$3_3") (pintype "bidirectional"))
      (node (ref "BUTTON") (pin "4") (pinfunction "P$4_4") (pintype "bidirectional"))
      (node (ref "C10") (pin "1") (pinfunction "1_1") (pintype "bidirectional"))
      (node (ref "C103") (pin "2") (pinfunction "2_2") (pintype "bidirectional"))
      (node (ref "C104") (pin "2") (pinfunction "2_2") (pintype "bidirectional"))
      (node (ref "C105") (pin "2") (pinfunction "2_2") (pintype "bidirectional"))
      (node (ref "C107") (pin "2") (pinfunction "2_2") (pintype "bidirectional"))
      (node (ref "C11") (pin "1") (pinfunction "1_1") (pintype "bidirectional"))
      (node (ref "C12") (pin "1") (pinfunction "1_1") (pintype "bidirectional"))
      (node (ref "C13") (pin "1") (pinfunction "1_1") (pintype "bidirectional"))
      (node (ref "C130") (pin "2") (pinfunction "2_2") (pintype "bidirectional"))
      (node (ref "C131") (pin "2") (pinfunction "2_2") (pintype "bidirectional"))
      (node (ref "C14") (pin "1") (pinfunction "1_1") (pintype "bidirectional"))
      (node (ref "C15") (pin "2") (pinfunction "2_2") (pintype "bidirectional"))
      (node (ref "C16") (pin "1") (pinfunction "1_1") (pintype "bidirectional"))
      (node (ref "C17") (pin "1") (pinfunction "1_1") (pintype "bidirectional"))
      (node (ref "C18") (pin "1") (pinfunction "1_1") (pintype "bidirectional"))
      (node (ref "C19") (pin "1") (pinfunction "1_1") (pintype "bidirectional"))
      (node (ref "C23") (pin "2") (pinfunction "2_2") (pintype "bidirectional"))
      (node (ref "C25") (pin "1") (pinfunction "1_1") (pintype "bidirectional"))
      (node (ref "C26") (pin "1") (pinfunction "1_1") (pintype "bidirectional"))
      (node (ref "C27") (pin "2") (pinfunction "2_2") (pintype "bidirectional"))
      (node (ref "C28") (pin "1") (pinfunction "1_1") (pintype "bidirectional"))
      (node (ref "C29") (pin "2") (pinfunction "2_2") (pintype "bidirectional"))
      (node (ref "C3") (pin "2") (pinfunction "2_2") (pintype "bidirectional"))
      (node (ref "C31") (pin "1") (pinfunction "1_1") (pintype "bidirectional"))
      (node (ref "C32") (pin "2") (pinfunction "2_2") (pintype "bidirectional"))
      (node (ref "C33") (pin "2") (pinfunction "2_2") (pintype "bidirectional"))
      (node (ref "C34") (pin "2") (pinfunction "2_2") (pintype "bidirectional"))
      (node (ref "C35") (pin "2") (pinfunction "2_2") (pintype "bidirectional"))
      (node (ref "C36") (pin "1") (pinfunction "1_1") (pintype "bidirectional"))
      (node (ref "C37") (pin "2") (pinfunction "2_2") (pintype "bidirectional"))
      (node (ref "C38") (pin "1") (pinfunction "1_1") (pintype "bidirectional"))
      (node (ref "C39") (pin "1") (pinfunction "1_1") (pintype "bidirectional"))
      (node (ref "C40") (pin "1") (pinfunction "1_1") (pintype "bidirectional"))
      (node (ref "C41") (pin "1") (pinfunction "1_1") (pintype "bidirectional"))
      (node (ref "C42") (pin "1") (pinfunction "1_1") (pintype "bidirectional"))
      (node (ref "C43") (pin "1") (pinfunction "1_1") (pintype "bidirectional"))
      (node (ref "C44") (pin "1") (pinfunction "1_1") (pintype "bidirectional"))
      (node (ref "C46") (pin "2") (pinfunction "2_2") (pintype "bidirectional"))
      (node (ref "C47") (pin "1") (pinfunction "1_1") (pintype "bidirectional"))
      (node (ref "C5") (pin "2") (pinfunction "2_2") (pintype "bidirectional"))
      (node (ref "C59") (pin "1") (pinfunction "1_1") (pintype "bidirectional"))
      (node (ref "C6") (pin "2") (pinfunction "2_2") (pintype "bidirectional"))
      (node (ref "C7") (pin "2") (pinfunction "2_2") (pintype "bidirectional"))
      (node (ref "C82") (pin "2") (pinfunction "2_2") (pintype "bidirectional"))
      (node (ref "C9") (pin "2") (pinfunction "2_2") (pintype "bidirectional"))
      (node (ref "D6") (pin "1") (pinfunction "1_1") (pintype "bidirectional"))
      (node (ref "DEBUG") (pin "3") (pinfunction "3_3") (pintype "bidirectional"))
      (node (ref "DEBUG") (pin "5") (pinfunction "5_5") (pintype "bidirectional"))
      (node (ref "DEBUG") (pin "9") (pinfunction "9_9") (pintype "bidirectional"))
      (node (ref "J4") (pin "1") (pinfunction "2_1") (pintype "passive"))
      (node (ref "P2") (pin "1") (pinfunction "1/GND_1") (pintype "bidirectional"))
      (node (ref "P2") (pin "13") (pinfunction "13/GND_13") (pintype "bidirectional"))
      (node (ref "P2") (pin "15") (pinfunction "15/GND_15") (pintype "bidirectional"))
      (node (ref "P2") (pin "25") (pinfunction "25/GND_25") (pintype "bidirectional"))
      (node (ref "P2") (pin "28") (pinfunction "28/GND_28") (pintype "bidirectional"))
      (node (ref "P2") (pin "37") (pinfunction "37/GND_37") (pintype "bidirectional"))
      (node (ref "P2") (pin "39") (pinfunction "39GND_39") (pintype "bidirectional"))
      (node (ref "P2") (pin "4") (pinfunction "4/GND_4") (pintype "bidirectional"))
      (node (ref "P2") (pin "59") (pinfunction "59/GND_59") (pintype "bidirectional"))
      (node (ref "P2") (pin "65") (pinfunction "65/GND_65") (pintype "bidirectional"))
      (node (ref "P2") (pin "66") (pinfunction "66/GND_66") (pintype "bidirectional"))
      (node (ref "P2") (pin "67") (pinfunction "67/GND_67") (pintype "bidirectional"))
      (node (ref "P2") (pin "68") (pinfunction "68/GND_68") (pintype "bidirectional"))
      (node (ref "P2") (pin "69") (pinfunction "69/GND_69") (pintype "bidirectional"))
      (node (ref "P2") (pin "70") (pinfunction "70/GND_70") (pintype "bidirectional"))
      (node (ref "P2") (pin "71") (pinfunction "71/GND_71") (pintype "bidirectional"))
      (node (ref "P2") (pin "72") (pinfunction "72/GND_72") (pintype "bidirectional"))
      (node (ref "P2") (pin "73") (pinfunction "73/GND_73") (pintype "bidirectional"))
      (node (ref "R10") (pin "2") (pinfunction "2_2") (pintype "bidirectional"))
      (node (ref "R12") (pin "1") (pinfunction "1_1") (pintype "bidirectional"))
      (node (ref "R14") (pin "2") (pinfunction "2_2") (pintype "bidirectional"))
      (node (ref "R17") (pin "1") (pinfunction "1_1") (pintype "bidirectional"))
      (node (ref "R2") (pin "2") (pinfunction "2_2") (pintype "bidirectional"))
      (node (ref "R21") (pin "2") (pinfunction "2_2") (pintype "bidirectional"))
      (node (ref "R22") (pin "1") (pinfunction "1_1") (pintype "bidirectional"))
      (node (ref "R25") (pin "1") (pinfunction "1_1") (pintype "bidirectional"))
      (node (ref "R26") (pin "1") (pinfunction "1_1") (pintype "bidirectional"))
      (node (ref "R28") (pin "1") (pinfunction "1_1") (pintype "bidirectional"))
      (node (ref "R31") (pin "2") (pinfunction "2_2") (pintype "bidirectional"))
      (node (ref "R33") (pin "2") (pinfunction "2_2") (pintype "bidirectional"))
      (node (ref "R35") (pin "2") (pinfunction "2_2") (pintype "bidirectional"))
      (node (ref "R37") (pin "1") (pinfunction "1_1") (pintype "bidirectional"))
      (node (ref "R40") (pin "1") (pinfunction "1_1") (pintype "bidirectional"))
      (node (ref "R44") (pin "1") (pinfunction "1_1") (pintype "bidirectional"))
      (node (ref "R45") (pin "2") (pinfunction "2_2") (pintype "bidirectional"))
      (node (ref "R49") (pin "2") (pinfunction "2_2") (pintype "bidirectional"))
      (node (ref "RESET") (pin "1") (pinfunction "P$1_1") (pintype "bidirectional"))
      (node (ref "RESET") (pin "2") (pinfunction "P$2_2") (pintype "bidirectional"))
      (node (ref "TP20") (pin "P$1") (pinfunction "1_P$1") (pintype "bidirectional"))
      (node (ref "TP21") (pin "P$1") (pinfunction "1_P$1") (pintype "bidirectional"))
      (node (ref "TP22") (pin "P$1") (pinfunction "1_P$1") (pintype "bidirectional"))
      (node (ref "TP23") (pin "P$1") (pinfunction "1_P$1") (pintype "bidirectional"))
      (node (ref "TP24") (pin "P$1") (pinfunction "1_P$1") (pintype "bidirectional"))
      (node (ref "U1") (pin "15") (pinfunction "PGND2_15") (pintype "bidirectional"))
      (node (ref "U1") (pin "2") (pinfunction "PGND1_2") (pintype "bidirectional"))
      (node (ref "U1") (pin "THERM") (pinfunction "PGND1_THERM") (pintype "bidirectional"))
      (node (ref "U10") (pin "10") (pinfunction "GND1_10") (pintype "bidirectional"))
      (node (ref "U10") (pin "11") (pinfunction "GND2_11") (pintype "bidirectional"))
      (node (ref "U10") (pin "12") (pinfunction "GND3_12") (pintype "bidirectional"))
      (node (ref "U10") (pin "13") (pinfunction "GND4_13") (pintype "bidirectional"))
      (node (ref "U10") (pin "6") (pinfunction "VSS_6") (pintype "power_in"))
      (node (ref "U13") (pin "4") (pinfunction "4GND_4") (pintype "bidirectional"))
      (node (ref "U2") (pin "2") (pinfunction "GND_2") (pintype "bidirectional"))
      (node (ref "U3") (pin "2") (pinfunction "GND_2") (pintype "bidirectional"))
      (node (ref "U4") (pin "5") (pinfunction "GND_5") (pintype "bidirectional"))
      (node (ref "U4") (pin "6") (pinfunction "GND_6") (pintype "bidirectional"))
      (node (ref "U4") (pin "7") (pinfunction "GND_7") (pintype "bidirectional"))
      (node (ref "U4") (pin "8") (pinfunction "GND_8") (pintype "bidirectional"))
      (node (ref "U5") (pin "11") (pinfunction "11GND2_11") (pintype "bidirectional"))
      (node (ref "U5") (pin "15") (pinfunction "15GND3_15") (pintype "bidirectional"))
      (node (ref "U5") (pin "3") (pinfunction "3GND1_3") (pintype "bidirectional"))
      (node (ref "U5") (pin "TH") (pinfunction "15GND3_TH") (pintype "bidirectional"))
      (node (ref "U6") (pin "5") (pinfunction "GND_5") (pintype "bidirectional"))
      (node (ref "U6") (pin "6") (pinfunction "GND_6") (pintype "bidirectional"))
      (node (ref "U6") (pin "7") (pinfunction "GND_7") (pintype "bidirectional"))
      (node (ref "U6") (pin "8") (pinfunction "GND_8") (pintype "bidirectional"))
      (node (ref "U7") (pin "11") (pinfunction "11GND2_11") (pintype "bidirectional"))
      (node (ref "U7") (pin "15") (pinfunction "15GND3_15") (pintype "bidirectional"))
      (node (ref "U7") (pin "3") (pinfunction "3GND1_3") (pintype "bidirectional"))
      (node (ref "U7") (pin "TH") (pinfunction "15GND3_TH") (pintype "bidirectional"))
      (node (ref "U9") (pin "2") (pinfunction "VSS_2") (pintype "bidirectional"))
      (node (ref "USB") (pin "4") (pinfunction "ID_4") (pintype "bidirectional"))
      (node (ref "USB") (pin "5") (pinfunction "GND3_5") (pintype "bidirectional"))
      (node (ref "USB") (pin "6") (pinfunction "GND_6") (pintype "bidirectional"))
      (node (ref "USB") (pin "7") (pinfunction "GND1_7") (pintype "bidirectional"))
      (node (ref "USB") (pin "8") (pinfunction "GND4_8") (pintype "bidirectional"))
      (node (ref "USB") (pin "9") (pinfunction "GND5_9") (pintype "bidirectional"))
    )
    (net (code "32") (name "GREEN") (class "Default")
      (node (ref "P2") (pin "32") (pinfunction "32/RGB-G_32") (pintype "bidirectional"))
      (node (ref "R7") (pin "1") (pinfunction "1_1") (pintype "bidirectional"))
    )
    (net (code "33") (name "I2S_AMP_SPEAKER_N_L") (class "Default")
      (node (ref "S2") (pin "6") (pinfunction "6_6") (pintype "bidirectional"))
      (node (ref "U7") (pin "10") (pinfunction "10OUTN_10") (pintype "bidirectional"))
    )
    (net (code "34") (name "I2S_AMP_SPEAKER_N_R") (class "Default")
      (node (ref "S3") (pin "6") (pinfunction "6_6") (pintype "bidirectional"))
      (node (ref "U5") (pin "10") (pinfunction "10OUTN_10") (pintype "bidirectional"))
    )
    (net (code "35") (name "I2S_AMP_SPEAKER_P_L") (class "Default")
      (node (ref "S2") (pin "3") (pinfunction "3_3") (pintype "bidirectional"))
      (node (ref "U7") (pin "9") (pinfunction "9OUTP_9") (pintype "bidirectional"))
    )
    (net (code "36") (name "I2S_AMP_SPEAKER_P_R") (class "Default")
      (node (ref "S3") (pin "3") (pinfunction "3_3") (pintype "bidirectional"))
      (node (ref "U5") (pin "9") (pinfunction "9OUTP_9") (pintype "bidirectional"))
    )
    (net (code "37") (name "I2S_BCLK") (class "Default")
      (node (ref "S6") (pin "1") (pinfunction "1_1") (pintype "bidirectional"))
      (node (ref "U5") (pin "16") (pinfunction "16BCLK_16") (pintype "bidirectional"))
      (node (ref "U7") (pin "16") (pinfunction "16BCLK_16") (pintype "bidirectional"))
    )
    (net (code "38") (name "I2S_BCLK{slash}AUDIO_R") (class "Default")
      (node (ref "P2") (pin "48") (pinfunction "48/S5_48") (pintype "bidirectional"))
      (node (ref "S6") (pin "3") (pinfunction "3_3") (pintype "bidirectional"))
      (node (ref "TP3") (pin "P$1") (pinfunction "1_P$1") (pintype "bidirectional"))
    )
    (net (code "39") (name "I2S_TX") (class "Default")
      (node (ref "P2") (pin "44") (pinfunction "44/S3_44") (pintype "bidirectional"))
      (node (ref "TP9") (pin "P$1") (pinfunction "1_P$1") (pintype "bidirectional"))
      (node (ref "U5") (pin "1") (pinfunction "1DIN_1") (pintype "bidirectional"))
      (node (ref "U7") (pin "1") (pinfunction "1DIN_1") (pintype "bidirectional"))
    )
    (net (code "40") (name "I2S_WS") (class "Default")
      (node (ref "S6") (pin "5") (pinfunction "5_5") (pintype "bidirectional"))
      (node (ref "U5") (pin "14") (pinfunction "14LRCLK_14") (pintype "bidirectional"))
      (node (ref "U7") (pin "14") (pinfunction "14LRCLK_14") (pintype "bidirectional"))
    )
    (net (code "41") (name "I2S_WS{slash}AUDIO_L") (class "Default")
      (node (ref "P2") (pin "33") (pinfunction "33/S6_33") (pintype "bidirectional"))
      (node (ref "S6") (pin "7") (pinfunction "7_7") (pintype "bidirectional"))
      (node (ref "TP7") (pin "P$1") (pinfunction "1_P$1") (pintype "bidirectional"))
    )
    (net (code "42") (name "MD") (class "Default")
      (node (ref "BUTTON") (pin "1") (pinfunction "P$1_1") (pintype "bidirectional"))
      (node (ref "BUTTON") (pin "2") (pinfunction "P$2_2") (pintype "bidirectional"))
      (node (ref "P2") (pin "46") (pinfunction "46/MODE_46") (pintype "bidirectional"))
    )
    (net (code "43") (name "Net-(C1-Pad1)") (class "Default")
      (node (ref "C1") (pin "1") (pinfunction "1_1") (pintype "bidirectional"))
      (node (ref "R46") (pin "1") (pinfunction "1_1") (pintype "bidirectional"))
    )
    (net (code "44") (name "Net-(C20-Pad1)") (class "Default")
      (node (ref "C20") (pin "1") (pinfunction "1_1") (pintype "bidirectional"))
      (node (ref "R50") (pin "1") (pinfunction "1_1") (pintype "bidirectional"))
    )
    (net (code "45") (name "Net-(C22-Pad1)") (class "Default")
      (node (ref "C22") (pin "1") (pinfunction "1_1") (pintype "bidirectional"))
      (node (ref "R38") (pin "1") (pinfunction "1_1") (pintype "bidirectional"))
    )
    (net (code "46") (name "Net-(C24-Pad1)") (class "Default")
      (node (ref "C24") (pin "1") (pinfunction "1_1") (pintype "bidirectional"))
      (node (ref "R39") (pin "1") (pinfunction "1_1") (pintype "bidirectional"))
    )
    (net (code "47") (name "Net-(C32-Pad1)") (class "Default")
      (node (ref "C32") (pin "1") (pinfunction "1_1") (pintype "bidirectional"))
      (node (ref "R4") (pin "1") (pinfunction "1_1") (pintype "bidirectional"))
    )
    (net (code "48") (name "Net-(CNG-K)") (class "Default")
      (node (ref "CNG") (pin "2") (pinfunction "K_2") (pintype "bidirectional"))
      (node (ref "R1") (pin "1") (pinfunction "1_1") (pintype "bidirectional"))
      (node (ref "R32") (pin "2") (pinfunction "2_2") (pintype "bidirectional"))
    )
    (net (code "49") (name "Net-(D1-P$1)") (class "Default")
      (node (ref "D1") (pin "1") (pinfunction "P$1_1") (pintype "bidirectional"))
      (node (ref "R34") (pin "1") (pinfunction "1_1") (pintype "bidirectional"))
    )
    (net (code "50") (name "Net-(D1-P$2)") (class "Default")
      (node (ref "D1") (pin "2") (pinfunction "P$2_2") (pintype "bidirectional"))
      (node (ref "DEBUG") (pin "1") (pinfunction "1_1") (pintype "bidirectional"))
    )
    (net (code "51") (name "Net-(D3-P$2)") (class "Default")
      (node (ref "C37") (pin "1") (pinfunction "1_1") (pintype "bidirectional"))
      (node (ref "D3") (pin "2") (pinfunction "P$2_2") (pintype "bidirectional"))
      (node (ref "U9") (pin "4") (pinfunction "VIN_4") (pintype "bidirectional"))
    )
    (net (code "52") (name "Net-(D4-P$1)") (class "Default")
      (node (ref "D4") (pin "1") (pinfunction "P$1_1") (pintype "bidirectional"))
      (node (ref "L1") (pin "P$2") (pinfunction "2_P$2") (pintype "passive"))
      (node (ref "U13") (pin "5") (pinfunction "SW_5") (pintype "bidirectional"))
    )
    (net (code "53") (name "Net-(F1-1)") (class "Default")
      (node (ref "D6") (pin "2") (pinfunction "2_2") (pintype "bidirectional"))
      (node (ref "F1") (pin "P$1") (pinfunction "1_P$1") (pintype "bidirectional"))
      (node (ref "USB") (pin "1") (pinfunction "VBUS_1") (pintype "bidirectional"))
    )
    (net (code "54") (name "Net-(J1-Pad1)") (class "Default")
      (node (ref "J1") (pin "1") (pinfunction "1_1") (pintype "passive"))
      (node (ref "S4") (pin "4") (pinfunction "4_4") (pintype "bidirectional"))
    )
    (net (code "55") (name "Net-(J1-Pad2)") (class "Default")
      (node (ref "J1") (pin "2") (pinfunction "2_2") (pintype "passive"))
      (node (ref "S4") (pin "1") (pinfunction "1_1") (pintype "bidirectional"))
    )
    (net (code "56") (name "Net-(J2-Pad1)") (class "Default")
      (node (ref "J2") (pin "1") (pinfunction "1_1") (pintype "passive"))
      (node (ref "S5") (pin "4") (pinfunction "4_4") (pintype "bidirectional"))
    )
    (net (code "57") (name "Net-(J2-Pad2)") (class "Default")
      (node (ref "J2") (pin "2") (pinfunction "2_2") (pintype "passive"))
      (node (ref "S5") (pin "1") (pinfunction "1_1") (pintype "bidirectional"))
    )
    (net (code "58") (name "Net-(J3-1)") (class "Default")
      (node (ref "J3") (pin "P$1") (pinfunction "1_P$1") (pintype "bidirectional"))
      (node (ref "R49") (pin "1") (pinfunction "1_1") (pintype "bidirectional"))
    )
    (net (code "59") (name "Net-(J3-2)") (class "Default")
      (node (ref "J3") (pin "P$2") (pinfunction "2_P$2") (pintype "bidirectional"))
      (node (ref "R22") (pin "2") (pinfunction "2_2") (pintype "bidirectional"))
    )
    (net (code "60") (name "Net-(J3-3)") (class "Default")
      (node (ref "C20") (pin "2") (pinfunction "2_2") (pintype "bidirectional"))
      (node (ref "J3") (pin "P$3") (pinfunction "3_P$3") (pintype "bidirectional"))
      (node (ref "J3") (pin "P$6") (pinfunction "6_P$6") (pintype "bidirectional"))
      (node (ref "TP16") (pin "P$1") (pinfunction "1_P$1") (pintype "bidirectional"))
    )
    (net (code "61") (name "Net-(J3-4)") (class "Default")
      (node (ref "C1") (pin "2") (pinfunction "2_2") (pintype "bidirectional"))
      (node (ref "J3") (pin "P$4") (pinfunction "4_P$4") (pintype "bidirectional"))
      (node (ref "J3") (pin "P$5") (pinfunction "5_P$5") (pintype "bidirectional"))
      (node (ref "TP17") (pin "P$1") (pinfunction "1_P$1") (pintype "bidirectional"))
    )
    (net (code "62") (name "Net-(L1-1)") (class "Default")
      (node (ref "C105") (pin "1") (pinfunction "1_1") (pintype "bidirectional"))
      (node (ref "C130") (pin "1") (pinfunction "1_1") (pintype "bidirectional"))
      (node (ref "C131") (pin "1") (pinfunction "1_1") (pintype "bidirectional"))
      (node (ref "C3") (pin "1") (pinfunction "1_1") (pintype "bidirectional"))
      (node (ref "C82") (pin "1") (pinfunction "1_1") (pintype "bidirectional"))
      (node (ref "L1") (pin "P$1") (pinfunction "1_P$1") (pintype "passive"))
      (node (ref "L22") (pin "1") (pinfunction "1_1") (pintype "bidirectional"))
      (node (ref "R55") (pin "1") (pinfunction "1_1") (pintype "bidirectional"))
      (node (ref "U13") (pin "6") (pinfunction "VIN_6") (pintype "bidirectional"))
      (node (ref "U13") (pin "7") (pinfunction "FREQ_7") (pintype "bidirectional"))
    )
    (net (code "63") (name "Net-(Q3-Pad1)") (class "Default")
      (node (ref "Q3") (pin "1") (pinfunction "1_1") (pintype "bidirectional"))
      (node (ref "R3") (pin "2") (pinfunction "2_2") (pintype "bidirectional"))
    )
    (net (code "64") (name "Net-(RGB-2)") (class "Default")
      (node (ref "R5") (pin "2") (pinfunction "2_2") (pintype "bidirectional"))
      (node (ref "RGB") (pin "BLUE") (pinfunction "2_BLUE") (pintype "passive"))
    )
    (net (code "65") (name "Net-(RGB-3)") (class "Default")
      (node (ref "R7") (pin "2") (pinfunction "2_2") (pintype "bidirectional"))
      (node (ref "RGB") (pin "GREEN") (pinfunction "3_GREEN") (pintype "passive"))
    )
    (net (code "66") (name "Net-(RGB-4)") (class "Default")
      (node (ref "R8") (pin "2") (pinfunction "2_2") (pintype "bidirectional"))
      (node (ref "RGB") (pin "RED") (pinfunction "4_RED") (pintype "passive"))
    )
    (net (code "67") (name "Net-(S2-Pad2)") (class "Default")
      (node (ref "S2") (pin "2") (pinfunction "2_2") (pintype "bidirectional"))
      (node (ref "S4") (pin "2") (pinfunction "2_2") (pintype "bidirectional"))
    )
    (net (code "68") (name "Net-(S2-Pad5)") (class "Default")
      (node (ref "S2") (pin "5") (pinfunction "5_5") (pintype "bidirectional"))
      (node (ref "S4") (pin "5") (pinfunction "5_5") (pintype "bidirectional"))
    )
    (net (code "69") (name "Net-(S3-Pad2)") (class "Default")
      (node (ref "S3") (pin "2") (pinfunction "2_2") (pintype "bidirectional"))
      (node (ref "S5") (pin "2") (pinfunction "2_2") (pintype "bidirectional"))
    )
    (net (code "70") (name "Net-(S3-Pad5)") (class "Default")
      (node (ref "S3") (pin "5") (pinfunction "5_5") (pintype "bidirectional"))
      (node (ref "S5") (pin "5") (pinfunction "5_5") (pintype "bidirectional"))
    )
    (net (code "71") (name "Net-(TP12-1)") (class "Default")
      (node (ref "TP12") (pin "P$1") (pinfunction "1_P$1") (pintype "bidirectional"))
      (node (ref "U10") (pin "9") (pinfunction "CD_9") (pintype "bidirectional"))
    )
    (net (code "72") (name "Net-(TP13-1)") (class "Default")
      (node (ref "R14") (pin "1") (pinfunction "1_1") (pintype "bidirectional"))
      (node (ref "R55") (pin "2") (pinfunction "2_2") (pintype "bidirectional"))
      (node (ref "TP13") (pin "P$1") (pinfunction "1_P$1") (pintype "bidirectional"))
      (node (ref "U13") (pin "3") (pinfunction "EN_3") (pintype "bidirectional"))
    )
    (net (code "73") (name "Net-(TP15-1)") (class "Default")
      (node (ref "TP15") (pin "P$1") (pinfunction "1_P$1") (pintype "bidirectional"))
      (node (ref "U10") (pin "1") (pinfunction "DAT2_1") (pintype "bidirectional"))
    )
    (net (code "74") (name "Net-(TP18-1)") (class "Default")
      (node (ref "TP18") (pin "P$1") (pinfunction "1_P$1") (pintype "bidirectional"))
      (node (ref "U10") (pin "8") (pinfunction "DAT1_8") (pintype "bidirectional"))
    )
    (net (code "75") (name "Net-(TP28-1)") (class "Default")
      (node (ref "R33") (pin "1") (pinfunction "1_1") (pintype "bidirectional"))
      (node (ref "R9") (pin "2") (pinfunction "2_2") (pintype "bidirectional"))
      (node (ref "TP28") (pin "P$1") (pinfunction "1_P$1") (pintype "bidirectional"))
      (node (ref "U1") (pin "12") (pinfunction "~{SHDN}_12") (pintype "bidirectional"))
    )
    (net (code "76") (name "Net-(TP29-1)") (class "Default")
      (node (ref "R13") (pin "2") (pinfunction "2_2") (pintype "bidirectional"))
      (node (ref "R45") (pin "1") (pinfunction "1_1") (pintype "bidirectional"))
      (node (ref "TP29") (pin "P$1") (pinfunction "1_P$1") (pintype "bidirectional"))
      (node (ref "U1") (pin "5") (pinfunction "~{MUTE}_5") (pintype "bidirectional"))
    )
    (net (code "77") (name "Net-(U1-GND)") (class "Default")
      (node (ref "R28") (pin "2") (pinfunction "2_2") (pintype "bidirectional"))
      (node (ref "U1") (pin "11") (pinfunction "GND_11") (pintype "bidirectional"))
    )
    (net (code "78") (name "Net-(U1-INL)") (class "Default")
      (node (ref "R38") (pin "2") (pinfunction "2_2") (pintype "bidirectional"))
      (node (ref "U1") (pin "7") (pinfunction "INL_7") (pintype "bidirectional"))
    )
    (net (code "79") (name "Net-(U1-INR)") (class "Default")
      (node (ref "R39") (pin "2") (pinfunction "2_2") (pintype "bidirectional"))
      (node (ref "U1") (pin "10") (pinfunction "INR_10") (pintype "bidirectional"))
    )
    (net (code "80") (name "Net-(U1-NC)") (class "Default")
      (node (ref "R40") (pin "2") (pinfunction "2_2") (pintype "bidirectional"))
      (node (ref "U1") (pin "9") (pinfunction "NC_9") (pintype "bidirectional"))
    )
    (net (code "81") (name "Net-(U1-VDD)") (class "Default")
      (node (ref "C10") (pin "2") (pinfunction "2_2") (pintype "bidirectional"))
      (node (ref "C11") (pin "2") (pinfunction "2_2") (pintype "bidirectional"))
      (node (ref "C12") (pin "2") (pinfunction "2_2") (pintype "bidirectional"))
      (node (ref "R27") (pin "2") (pinfunction "2_2") (pintype "bidirectional"))
      (node (ref "U1") (pin "6") (pinfunction "VDD_6") (pintype "bidirectional"))
    )
    (net (code "82") (name "Net-(U1-VREF)") (class "Default")
      (node (ref "C23") (pin "1") (pinfunction "1_1") (pintype "bidirectional"))
      (node (ref "R31") (pin "1") (pinfunction "1_1") (pintype "bidirectional"))
      (node (ref "R6") (pin "1") (pinfunction "1_1") (pintype "bidirectional"))
      (node (ref "U1") (pin "8") (pinfunction "VREF_8") (pintype "bidirectional"))
    )
    (net (code "83") (name "Net-(U2-EN)") (class "Default")
      (node (ref "R18") (pin "2") (pinfunction "2_2") (pintype "bidirectional"))
      (node (ref "U2") (pin "5") (pinfunction "EN_5") (pintype "bidirectional"))
    )
    (net (code "84") (name "Net-(U3-IN)") (class "Default")
      (node (ref "C7") (pin "1") (pinfunction "1_1") (pintype "bidirectional"))
      (node (ref "R17") (pin "2") (pinfunction "2_2") (pintype "bidirectional"))
      (node (ref "R29") (pin "2") (pinfunction "2_2") (pintype "bidirectional"))
      (node (ref "R30") (pin "2") (pinfunction "2_2") (pintype "bidirectional"))
      (node (ref "U3") (pin "3") (pinfunction "IN_3") (pintype "bidirectional"))
    )
    (net (code "85") (name "Net-(U4-LR)") (class "Default")
      (node (ref "R37") (pin "2") (pinfunction "2_2") (pintype "bidirectional"))
      (node (ref "U4") (pin "2") (pinfunction "LR_2") (pintype "bidirectional"))
    )
    (net (code "86") (name "Net-(U5-2GAIN_SLOT)") (class "Default")
      (node (ref "R11") (pin "2") (pinfunction "2_2") (pintype "bidirectional"))
      (node (ref "R12") (pin "2") (pinfunction "2_2") (pintype "bidirectional"))
      (node (ref "U5") (pin "2") (pinfunction "2GAIN_SLOT_2") (pintype "bidirectional"))
    )
    (net (code "87") (name "Net-(U5-4~{SD_MODE})") (class "Default")
      (node (ref "R15") (pin "2") (pinfunction "2_2") (pintype "bidirectional"))
      (node (ref "U5") (pin "4") (pinfunction "4~{SD_MODE}_4") (pintype "bidirectional"))
    )
    (net (code "88") (name "Net-(U6-LR)") (class "Default")
      (node (ref "R36") (pin "1") (pinfunction "1_1") (pintype "bidirectional"))
      (node (ref "U6") (pin "2") (pinfunction "LR_2") (pintype "bidirectional"))
    )
    (net (code "89") (name "Net-(U7-2GAIN_SLOT)") (class "Default")
      (node (ref "R43") (pin "2") (pinfunction "2_2") (pintype "bidirectional"))
      (node (ref "R44") (pin "2") (pinfunction "2_2") (pintype "bidirectional"))
      (node (ref "U7") (pin "2") (pinfunction "2GAIN_SLOT_2") (pintype "bidirectional"))
    )
    (net (code "90") (name "Net-(U7-4~{SD_MODE})") (class "Default")
      (node (ref "R42") (pin "2") (pinfunction "2_2") (pintype "bidirectional"))
      (node (ref "U7") (pin "4") (pinfunction "4~{SD_MODE}_4") (pintype "bidirectional"))
    )
    (net (code "91") (name "Net-(U9-ISEN)") (class "Default")
      (node (ref "R2") (pin "1") (pinfunction "1_1") (pintype "bidirectional"))
      (node (ref "U9") (pin "5") (pinfunction "ISEN_5") (pintype "bidirectional"))
    )
    (net (code "92") (name "Net-(U9-{slash}CHG)") (class "Default")
      (node (ref "R32") (pin "1") (pinfunction "1_1") (pintype "bidirectional"))
      (node (ref "R35") (pin "1") (pinfunction "1_1") (pintype "bidirectional"))
      (node (ref "U9") (pin "1") (pinfunction "/CHG_1") (pintype "bidirectional"))
    )
    (net (code "93") (name "Net-(U13-CMMP)") (class "Default")
      (node (ref "R4") (pin "2") (pinfunction "2_2") (pintype "bidirectional"))
      (node (ref "U13") (pin "1") (pinfunction "CMMP_1") (pintype "bidirectional"))
    )
    (net (code "94") (name "Net-(U13-FB)") (class "Default")
      (node (ref "C45") (pin "1") (pinfunction "1_1") (pintype "bidirectional"))
      (node (ref "R24") (pin "2") (pinfunction "2_2") (pintype "bidirectional"))
      (node (ref "R25") (pin "2") (pinfunction "2_2") (pintype "bidirectional"))
      (node (ref "U13") (pin "2") (pinfunction "FB_2") (pintype "bidirectional"))
    )
    (net (code "95") (name "Net-(U13-SS)") (class "Default")
      (node (ref "C33") (pin "1") (pinfunction "1_1") (pintype "bidirectional"))
      (node (ref "U13") (pin "8") (pinfunction "SS_8") (pintype "bidirectional"))
    )
    (net (code "96") (name "RED") (class "Default")
      (node (ref "P2") (pin "29") (pinfunction "29/RGB-R_29") (pintype "bidirectional"))
      (node (ref "R8") (pin "1") (pinfunction "1_1") (pintype "bidirectional"))
    )
    (net (code "97") (name "SCL") (class "Default")
      (node (ref "P2") (pin "35") (pinfunction "35/D1_35") (pintype "bidirectional"))
      (node (ref "TP11") (pin "P$1") (pinfunction "1_P$1") (pintype "bidirectional"))
    )
    (net (code "98") (name "SDA") (class "Default")
      (node (ref "P2") (pin "36") (pinfunction "36/D0_36") (pintype "bidirectional"))
      (node (ref "TP6") (pin "P$1") (pinfunction "1_P$1") (pintype "bidirectional"))
    )
    (net (code "99") (name "SPI1_CS_SD") (class "Default")
      (node (ref "P2") (pin "53") (pinfunction "53/D5_53") (pintype "bidirectional"))
      (node (ref "TP14") (pin "P$1") (pinfunction "1_P$1") (pintype "bidirectional"))
      (node (ref "U10") (pin "2") (pinfunction "CD/DAT3_2") (pintype "bidirectional"))
    )
    (net (code "100") (name "SPI1_MISO_SD") (class "Default")
      (node (ref "P2") (pin "51") (pinfunction "51/D3_51") (pintype "bidirectional"))
      (node (ref "R16") (pin "2") (pinfunction "2_2") (pintype "bidirectional"))
      (node (ref "TP2") (pin "P$1") (pinfunction "1_P$1") (pintype "bidirectional"))
      (node (ref "U10") (pin "7") (pinfunction "DAT0_7") (pintype "bidirectional"))
    )
    (net (code "101") (name "SPI1_MOSI_SD") (class "Default")
      (node (ref "P2") (pin "45") (pinfunction "45/D2_45") (pintype "bidirectional"))
      (node (ref "R23") (pin "2") (pinfunction "2_2") (pintype "bidirectional"))
      (node (ref "TP8") (pin "P$1") (pinfunction "1_P$1") (pintype "bidirectional"))
      (node (ref "U10") (pin "3") (pinfunction "CMD_3") (pintype "power_in"))
    )
    (net (code "102") (name "SPI1_SCK_SD") (class "Default")
      (node (ref "P2") (pin "52") (pinfunction "52/D4_52") (pintype "bidirectional"))
      (node (ref "R19") (pin "2") (pinfunction "2_2") (pintype "bidirectional"))
      (node (ref "TP19") (pin "P$1") (pinfunction "1_P$1") (pintype "bidirectional"))
      (node (ref "U10") (pin "5") (pinfunction "CLK_5") (pintype "power_in"))
    )
    (net (code "103") (name "SW") (class "Default")
      (node (ref "L2") (pin "P$1") (pinfunction "1_P$1") (pintype "passive"))
      (node (ref "U2") (pin "4") (pinfunction "SW_4") (pintype "bidirectional"))
    )
    (net (code "104") (name "VBAT") (class "Default")
      (node (ref "C25") (pin "2") (pinfunction "2_2") (pintype "bidirectional"))
      (node (ref "J4") (pin "2") (pinfunction "1_2") (pintype "passive"))
      (node (ref "Q3") (pin "3") (pinfunction "3_3") (pintype "bidirectional"))
      (node (ref "U9") (pin "3") (pinfunction "VBAT_3") (pintype "bidirectional"))
    )
    (net (code "105") (name "VBAT_MEAS") (class "Default")
      (node (ref "P2") (pin "12") (pinfunction "12/VBAT_MEAS_12") (pintype "bidirectional"))
      (node (ref "TP4") (pin "P$1") (pinfunction "1_P$1") (pintype "bidirectional"))
    )
    (net (code "106") (name "VIN") (class "Default")
      (node (ref "C40") (pin "2") (pinfunction "2_2") (pintype "bidirectional"))
      (node (ref "C46") (pin "1") (pinfunction "1_1") (pintype "bidirectional"))
      (node (ref "C5") (pin "1") (pinfunction "1_1") (pintype "bidirectional"))
      (node (ref "C6") (pin "1") (pinfunction "1_1") (pintype "bidirectional"))
      (node (ref "D2") (pin "CATHODE") (pinfunction "CATHODE_CATHODE") (pintype "bidirectional"))
      (node (ref "L22") (pin "2") (pinfunction "2_2") (pintype "bidirectional"))
      (node (ref "Q3") (pin "2") (pinfunction "2_2") (pintype "bidirectional"))
      (node (ref "R30") (pin "1") (pinfunction "1_1") (pintype "bidirectional"))
      (node (ref "R54") (pin "2") (pinfunction "2_2") (pintype "bidirectional"))
      (node (ref "U2") (pin "3") (pinfunction "VIN_3") (pintype "bidirectional"))
    )
    (net (code "107") (name "VUSB") (class "Default")
      (node (ref "CNG") (pin "1") (pinfunction "A_1") (pintype "bidirectional"))
      (node (ref "D2") (pin "ANODE") (pinfunction "ANODE_ANODE") (pintype "bidirectional"))
      (node (ref "D3") (pin "1") (pinfunction "P$1_1") (pintype "bidirectional"))
      (node (ref "F1") (pin "P$2") (pinfunction "2_P$2") (pintype "bidirectional"))
      (node (ref "R1") (pin "2") (pinfunction "2_2") (pintype "bidirectional"))
      (node (ref "R26") (pin "2") (pinfunction "2_2") (pintype "bidirectional"))
      (node (ref "R3") (pin "1") (pinfunction "1_1") (pintype "bidirectional"))
    )
    (net (code "108") (name "unconnected-(DEBUG-Pad6)") (class "Default")
      (node (ref "DEBUG") (pin "6") (pinfunction "6_6") (pintype "bidirectional"))
    )
    (net (code "109") (name "unconnected-(DEBUG-Pad7)") (class "Default")
      (node (ref "DEBUG") (pin "7") (pinfunction "7_7") (pintype "bidirectional"))
    )
    (net (code "110") (name "unconnected-(DEBUG-Pad8)") (class "Default")
      (node (ref "DEBUG") (pin "8") (pinfunction "8_8") (pintype "bidirectional"))
    )
    (net (code "111") (name "unconnected-(P2-6{slash}NC-Pad6)") (class "Default")
      (node (ref "P2") (pin "6") (pinfunction "6/NC_6") (pintype "bidirectional"))
    )
    (net (code "112") (name "unconnected-(P2-7{slash}NC-Pad7)") (class "Default")
      (node (ref "P2") (pin "7") (pinfunction "7/NC_7") (pintype "bidirectional"))
    )
    (net (code "113") (name "unconnected-(P2-8{slash}NC-Pad8)") (class "Default")
      (node (ref "P2") (pin "8") (pinfunction "8/NC_8") (pintype "bidirectional"))
    )
    (net (code "114") (name "unconnected-(P2-9{slash}NC-Pad9)") (class "Default")
      (node (ref "P2") (pin "9") (pinfunction "9/NC_9") (pintype "bidirectional"))
    )
    (net (code "115") (name "unconnected-(P2-10{slash}NC-Pad10)") (class "Default")
      (node (ref "P2") (pin "10") (pinfunction "10/NC_10") (pintype "bidirectional"))
    )
    (net (code "116") (name "unconnected-(P2-11{slash}NC-Pad11)") (class "Default")
      (node (ref "P2") (pin "11") (pinfunction "11/NC_11") (pintype "bidirectional"))
    )
    (net (code "117") (name "unconnected-(P2-14{slash}NC-Pad14)") (class "Default")
      (node (ref "P2") (pin "14") (pinfunction "14/NC_14") (pintype "bidirectional"))
    )
    (net (code "118") (name "unconnected-(P2-16{slash}NC-Pad16)") (class "Default")
      (node (ref "P2") (pin "16") (pinfunction "16/NC_16") (pintype "bidirectional"))
    )
    (net (code "119") (name "unconnected-(P2-17{slash}NC-Pad17)") (class "Default")
      (node (ref "P2") (pin "17") (pinfunction "17/NC_17") (pintype "bidirectional"))
    )
    (net (code "120") (name "unconnected-(P2-18{slash}NC-Pad18)") (class "Default")
      (node (ref "P2") (pin "18") (pinfunction "18/NC_18") (pintype "bidirectional"))
    )
    (net (code "121") (name "unconnected-(P2-19{slash}NC-Pad19)") (class "Default")
      (node (ref "P2") (pin "19") (pinfunction "19/NC_19") (pintype "bidirectional"))
    )
    (net (code "122") (name "unconnected-(P2-20{slash}NC-Pad20)") (class "Default")
      (node (ref "P2") (pin "20") (pinfunction "20/NC_20") (pintype "bidirectional"))
    )
    (net (code "123") (name "unconnected-(P2-21{slash}NC-Pad21)") (class "Default")
      (node (ref "P2") (pin "21") (pinfunction "21/NC_21") (pintype "bidirectional"))
    )
    (net (code "124") (name "unconnected-(P2-22{slash}NC-Pad22)") (class "Default")
      (node (ref "P2") (pin "22") (pinfunction "22/NC_22") (pintype "bidirectional"))
    )
    (net (code "125") (name "unconnected-(P2-38{slash}NC-Pad38)") (class "Default")
      (node (ref "P2") (pin "38") (pinfunction "38/NC_38") (pintype "bidirectional"))
    )
    (net (code "126") (name "unconnected-(P2-56{slash}NC-Pad56)") (class "Default")
      (node (ref "P2") (pin "56") (pinfunction "56/NC_56") (pintype "bidirectional"))
    )
    (net (code "127") (name "unconnected-(P2-57{slash}NC-Pad57)") (class "Default")
      (node (ref "P2") (pin "57") (pinfunction "57/NC_57") (pintype "bidirectional"))
    )
    (net (code "128") (name "unconnected-(P2-58{slash}NC-Pad58)") (class "Default")
      (node (ref "P2") (pin "58") (pinfunction "58/NC_58") (pintype "bidirectional"))
    )
    (net (code "129") (name "unconnected-(P2-60{slash}NC-Pad60)") (class "Default")
      (node (ref "P2") (pin "60") (pinfunction "60/NC_60") (pintype "bidirectional"))
    )
    (net (code "130") (name "unconnected-(P2-74{slash}NC-Pad74)") (class "Default")
      (node (ref "P2") (pin "74") (pinfunction "74/NC_74") (pintype "bidirectional"))
    )
    (net (code "131") (name "unconnected-(P2-75{slash}NC-Pad75)") (class "Default")
      (node (ref "P2") (pin "75") (pinfunction "75/NC_75") (pintype "bidirectional"))
    )
    (net (code "132") (name "unconnected-(S4-Pad3)") (class "Default")
      (node (ref "S4") (pin "3") (pinfunction "3_3") (pintype "bidirectional"))
    )
    (net (code "133") (name "unconnected-(S4-Pad6)") (class "Default")
      (node (ref "S4") (pin "6") (pinfunction "6_6") (pintype "bidirectional"))
    )
    (net (code "134") (name "unconnected-(S5-Pad3)") (class "Default")
      (node (ref "S5") (pin "3") (pinfunction "3_3") (pintype "bidirectional"))
    )
    (net (code "135") (name "unconnected-(S5-Pad6)") (class "Default")
      (node (ref "S5") (pin "6") (pinfunction "6_6") (pintype "bidirectional"))
    )
    (net (code "136") (name "unconnected-(U5-5NC-Pad5)") (class "Default")
      (node (ref "U5") (pin "5") (pinfunction "5NC_5") (pintype "bidirectional"))
    )
    (net (code "137") (name "unconnected-(U5-6NC2-Pad6)") (class "Default")
      (node (ref "U5") (pin "6") (pinfunction "6NC2_6") (pintype "bidirectional"))
    )
    (net (code "138") (name "unconnected-(U5-12NC3-Pad12)") (class "Default")
      (node (ref "U5") (pin "12") (pinfunction "12NC3_12") (pintype "bidirectional"))
    )
    (net (code "139") (name "unconnected-(U5-13NC4-Pad13)") (class "Default")
      (node (ref "U5") (pin "13") (pinfunction "13NC4_13") (pintype "bidirectional"))
    )
    (net (code "140") (name "unconnected-(U7-5NC-Pad5)") (class "Default")
      (node (ref "U7") (pin "5") (pinfunction "5NC_5") (pintype "bidirectional"))
    )
    (net (code "141") (name "unconnected-(U7-6NC2-Pad6)") (class "Default")
      (node (ref "U7") (pin "6") (pinfunction "6NC2_6") (pintype "bidirectional"))
    )
    (net (code "142") (name "unconnected-(U7-12NC3-Pad12)") (class "Default")
      (node (ref "U7") (pin "12") (pinfunction "12NC3_12") (pintype "bidirectional"))
    )
    (net (code "143") (name "unconnected-(U7-13NC4-Pad13)") (class "Default")
      (node (ref "U7") (pin "13") (pinfunction "13NC4_13") (pintype "bidirectional"))
    )
    (net (code "144") (name "{slash}RST") (class "Default")
      (node (ref "DEBUG") (pin "10") (pinfunction "10_10") (pintype "bidirectional"))
      (node (ref "P2") (pin "34") (pinfunction "34/RESET_34") (pintype "bidirectional"))
      (node (ref "RESET") (pin "3") (pinfunction "P$3_3") (pintype "bidirectional"))
      (node (ref "RESET") (pin "4") (pinfunction "P$4_4") (pintype "bidirectional"))
      (node (ref "U3") (pin "1") (pinfunction "OUT_1") (pintype "bidirectional"))
    )
  )
)
